# LED-plus35-SHIM.net
KiCad netlist of a schematic drawn in EAGLE
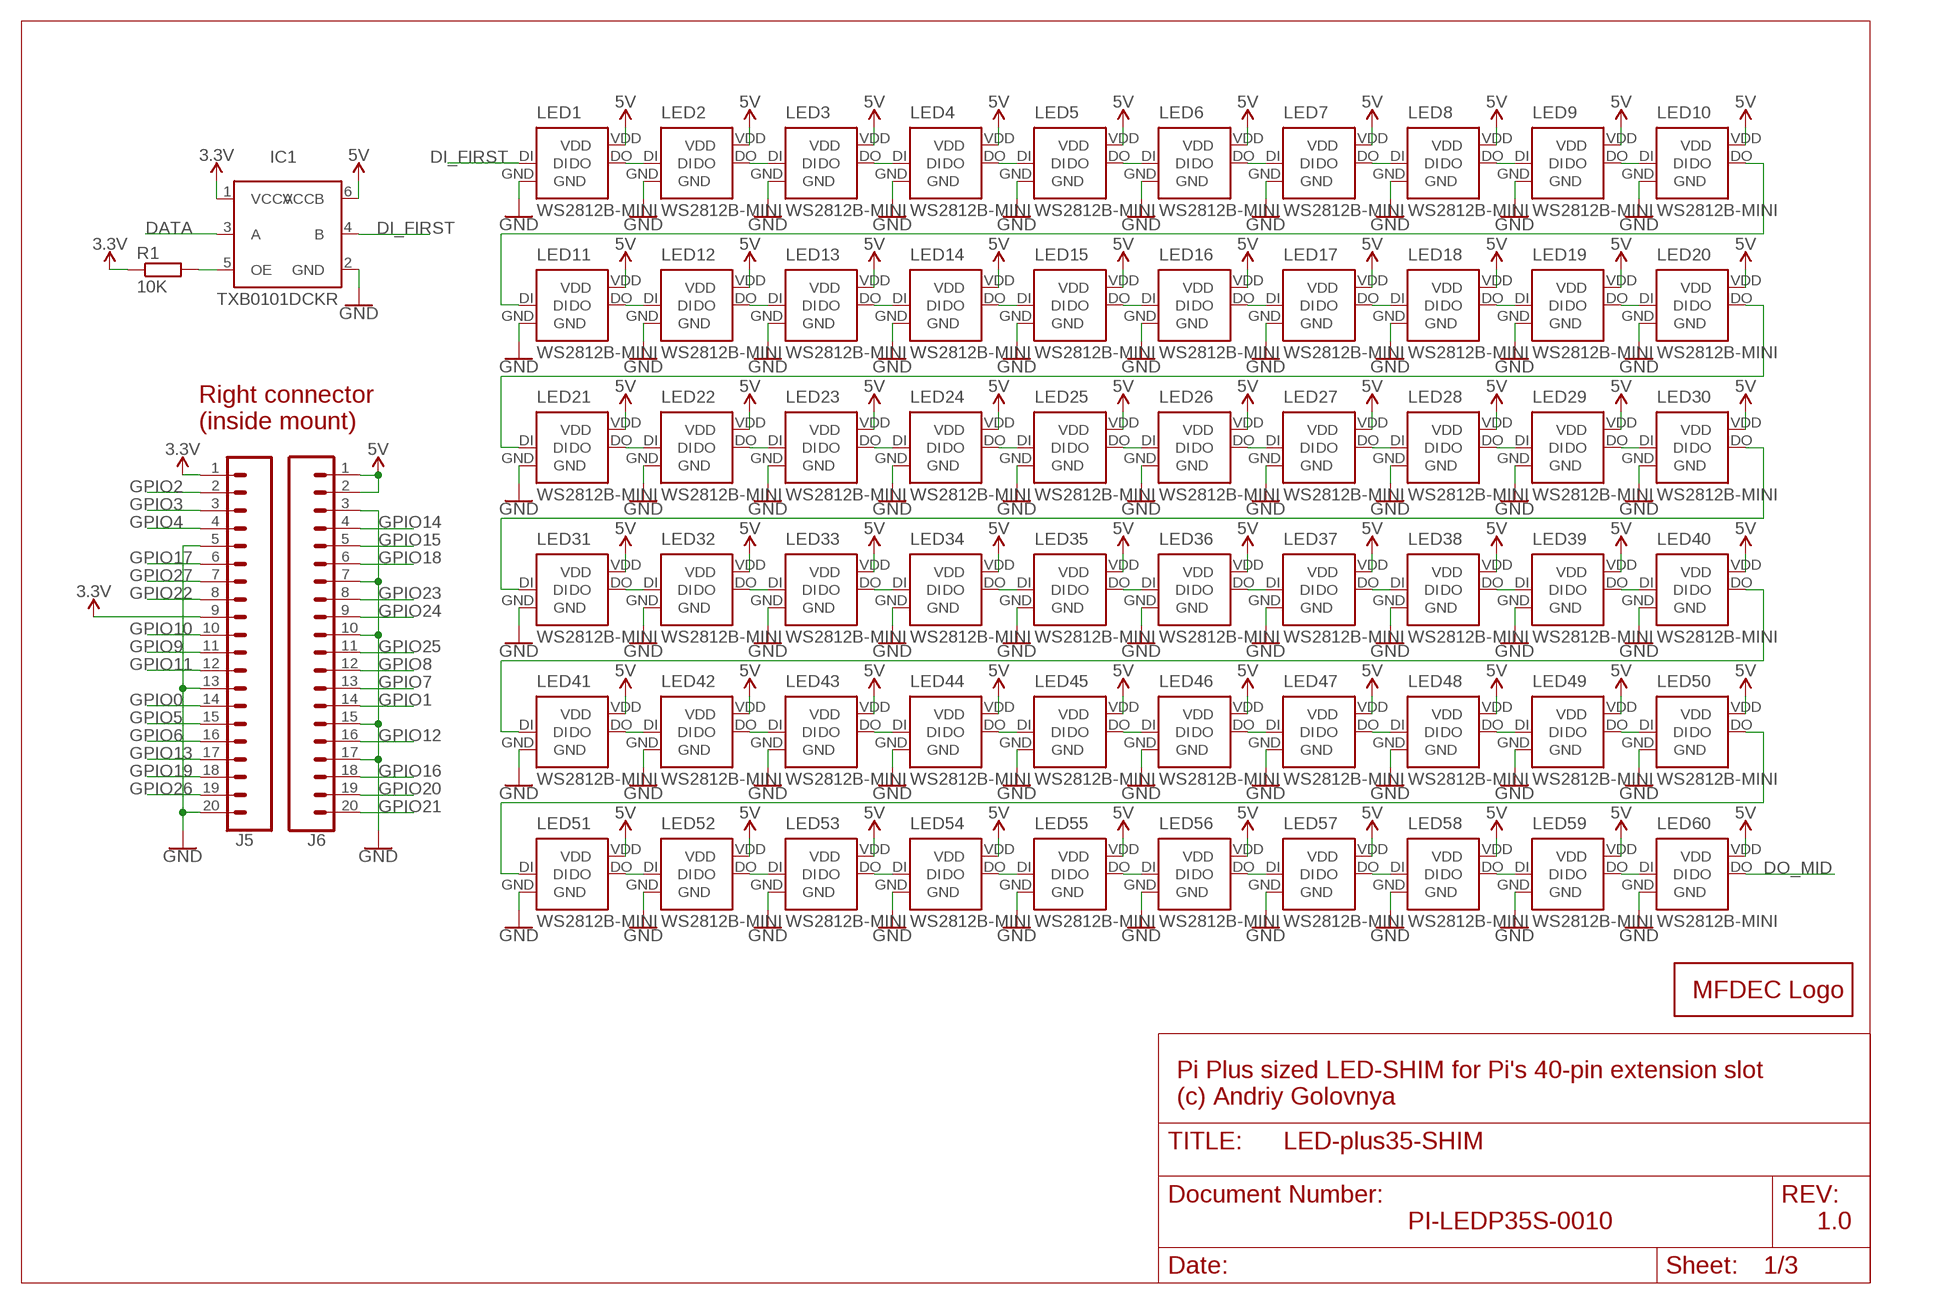
[diagram p0: schematic, sheet 1]
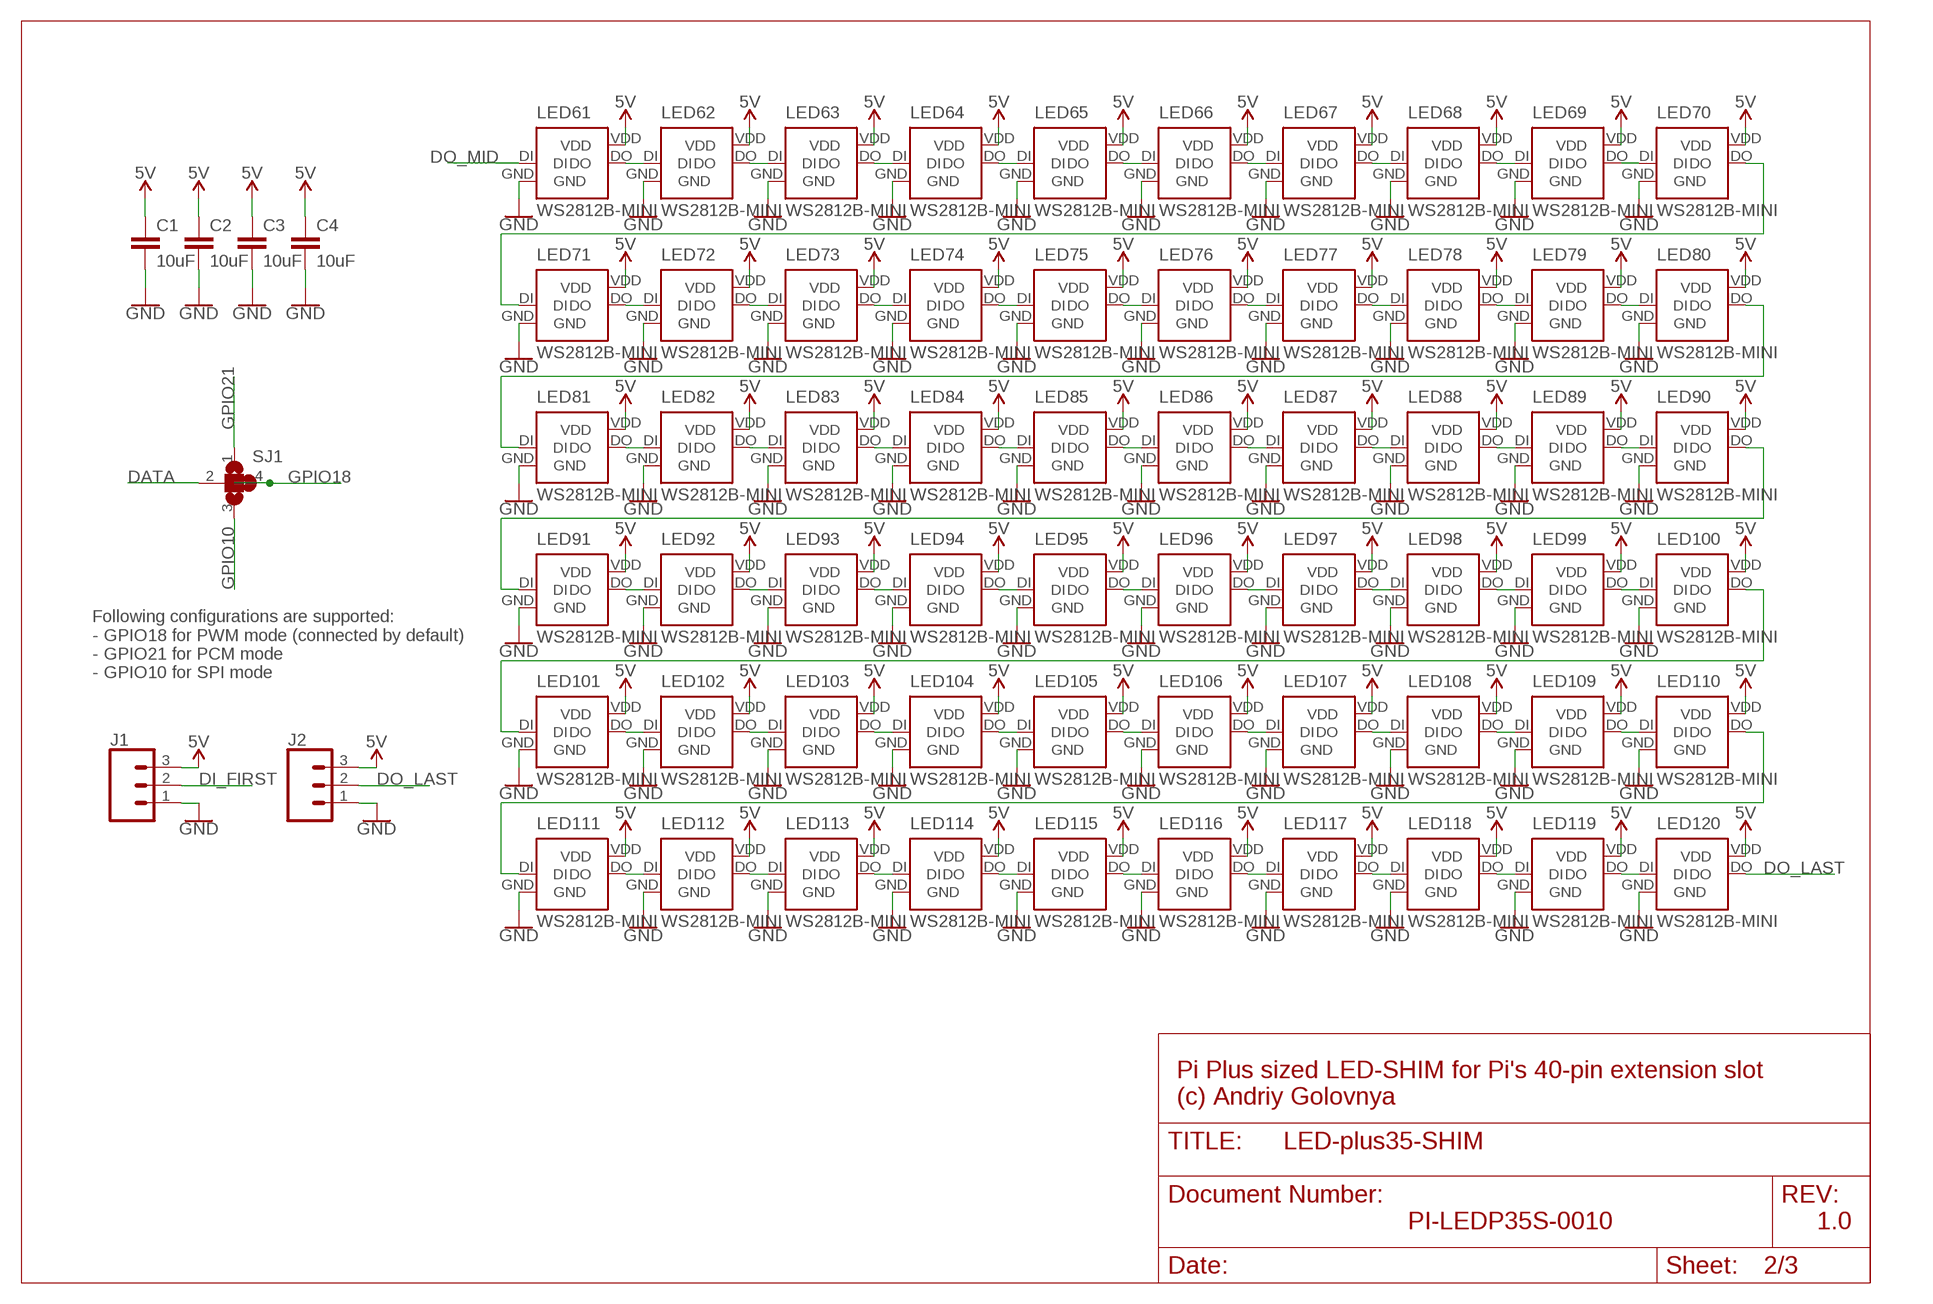
[diagram p1: schematic, sheet 2]
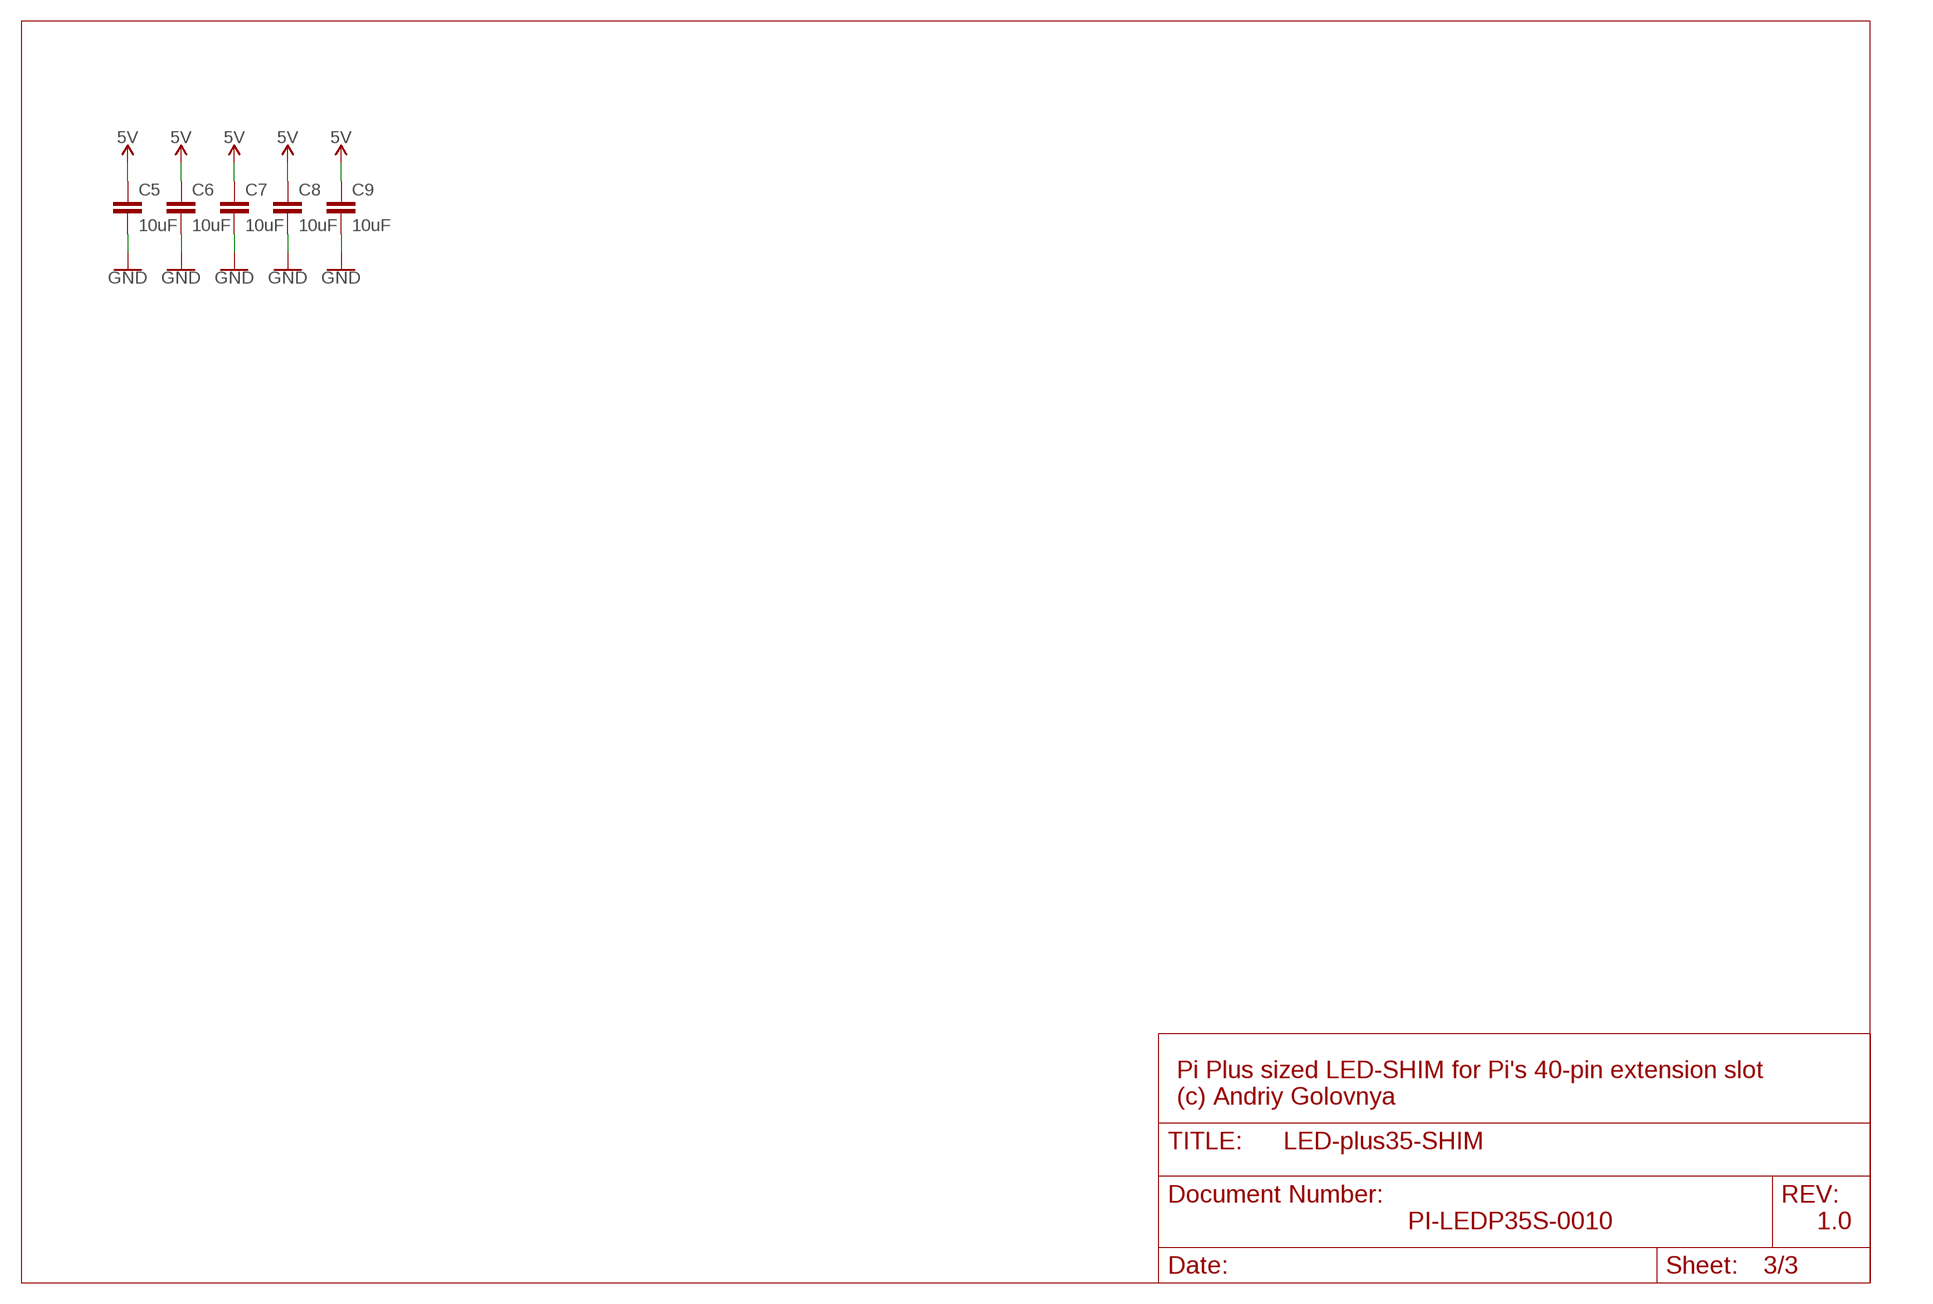
[diagram p2: schematic, sheet 3]

(export (version "E")
  (design (tool "Eeschema 10.0.6"))
  (components
    (comp (ref "C5")
      (value "10uF")
      (footprint "eagle-import:C0805")
      (libsource (lib "eagle-import") (part "C-EUC0805"))
    )
    (comp (ref "C6")
      (value "10uF")
      (footprint "eagle-import:C0805")
      (libsource (lib "eagle-import") (part "C-EUC0805"))
    )
    (comp (ref "C7")
      (value "10uF")
      (footprint "eagle-import:C0805")
      (libsource (lib "eagle-import") (part "C-EUC0805"))
    )
    (comp (ref "C8")
      (value "10uF")
      (footprint "eagle-import:C0805")
      (libsource (lib "eagle-import") (part "C-EUC0805"))
    )
    (comp (ref "C9")
      (value "10uF")
      (footprint "eagle-import:C0805")
      (libsource (lib "eagle-import") (part "C-EUC0805"))
    )
    (comp (ref "IC1")
      (value "TXB0101DCKR")
      (footprint "eagle-import:SOT65P210X110-6N")
      (libsource (lib "eagle-import") (part "TXB0101DCKR"))
    )
    (comp (ref "J5")
      (value "CONN_20LOCK")
      (footprint "eagle-import:1X20_LOCK")
      (libsource (lib "eagle-import") (part "CONN_20LOCK"))
    )
    (comp (ref "J6")
      (value "CONN_20LOCK")
      (footprint "eagle-import:1X20_LOCK")
      (libsource (lib "eagle-import") (part "CONN_20LOCK"))
    )
    (comp (ref "LED1")
      (value "WS2812B-MINI")
      (footprint "eagle-import:WS2812X-MINI")
      (libsource (lib "eagle-import") (part "WS2812B-MINI"))
    )
    (comp (ref "LED2")
      (value "WS2812B-MINI")
      (footprint "eagle-import:WS2812X-MINI")
      (libsource (lib "eagle-import") (part "WS2812B-MINI"))
    )
    (comp (ref "LED3")
      (value "WS2812B-MINI")
      (footprint "eagle-import:WS2812X-MINI")
      (libsource (lib "eagle-import") (part "WS2812B-MINI"))
    )
    (comp (ref "LED4")
      (value "WS2812B-MINI")
      (footprint "eagle-import:WS2812X-MINI")
      (libsource (lib "eagle-import") (part "WS2812B-MINI"))
    )
    (comp (ref "LED5")
      (value "WS2812B-MINI")
      (footprint "eagle-import:WS2812X-MINI")
      (libsource (lib "eagle-import") (part "WS2812B-MINI"))
    )
    (comp (ref "LED6")
      (value "WS2812B-MINI")
      (footprint "eagle-import:WS2812X-MINI")
      (libsource (lib "eagle-import") (part "WS2812B-MINI"))
    )
    (comp (ref "LED7")
      (value "WS2812B-MINI")
      (footprint "eagle-import:WS2812X-MINI")
      (libsource (lib "eagle-import") (part "WS2812B-MINI"))
    )
    (comp (ref "LED8")
      (value "WS2812B-MINI")
      (footprint "eagle-import:WS2812X-MINI")
      (libsource (lib "eagle-import") (part "WS2812B-MINI"))
    )
    (comp (ref "LED9")
      (value "WS2812B-MINI")
      (footprint "eagle-import:WS2812X-MINI")
      (libsource (lib "eagle-import") (part "WS2812B-MINI"))
    )
    (comp (ref "LED10")
      (value "WS2812B-MINI")
      (footprint "eagle-import:WS2812X-MINI")
      (libsource (lib "eagle-import") (part "WS2812B-MINI"))
    )
    (comp (ref "LED11")
      (value "WS2812B-MINI")
      (footprint "eagle-import:WS2812X-MINI")
      (libsource (lib "eagle-import") (part "WS2812B-MINI"))
    )
    (comp (ref "LED12")
      (value "WS2812B-MINI")
      (footprint "eagle-import:WS2812X-MINI")
      (libsource (lib "eagle-import") (part "WS2812B-MINI"))
    )
    (comp (ref "LED13")
      (value "WS2812B-MINI")
      (footprint "eagle-import:WS2812X-MINI")
      (libsource (lib "eagle-import") (part "WS2812B-MINI"))
    )
    (comp (ref "LED14")
      (value "WS2812B-MINI")
      (footprint "eagle-import:WS2812X-MINI")
      (libsource (lib "eagle-import") (part "WS2812B-MINI"))
    )
    (comp (ref "LED15")
      (value "WS2812B-MINI")
      (footprint "eagle-import:WS2812X-MINI")
      (libsource (lib "eagle-import") (part "WS2812B-MINI"))
    )
    (comp (ref "LED16")
      (value "WS2812B-MINI")
      (footprint "eagle-import:WS2812X-MINI")
      (libsource (lib "eagle-import") (part "WS2812B-MINI"))
    )
    (comp (ref "LED17")
      (value "WS2812B-MINI")
      (footprint "eagle-import:WS2812X-MINI")
      (libsource (lib "eagle-import") (part "WS2812B-MINI"))
    )
    (comp (ref "LED18")
      (value "WS2812B-MINI")
      (footprint "eagle-import:WS2812X-MINI")
      (libsource (lib "eagle-import") (part "WS2812B-MINI"))
    )
    (comp (ref "LED19")
      (value "WS2812B-MINI")
      (footprint "eagle-import:WS2812X-MINI")
      (libsource (lib "eagle-import") (part "WS2812B-MINI"))
    )
    (comp (ref "LED20")
      (value "WS2812B-MINI")
      (footprint "eagle-import:WS2812X-MINI")
      (libsource (lib "eagle-import") (part "WS2812B-MINI"))
    )
    (comp (ref "LED21")
      (value "WS2812B-MINI")
      (footprint "eagle-import:WS2812X-MINI")
      (libsource (lib "eagle-import") (part "WS2812B-MINI"))
    )
    (comp (ref "LED22")
      (value "WS2812B-MINI")
      (footprint "eagle-import:WS2812X-MINI")
      (libsource (lib "eagle-import") (part "WS2812B-MINI"))
    )
    (comp (ref "LED23")
      (value "WS2812B-MINI")
      (footprint "eagle-import:WS2812X-MINI")
      (libsource (lib "eagle-import") (part "WS2812B-MINI"))
    )
    (comp (ref "LED24")
      (value "WS2812B-MINI")
      (footprint "eagle-import:WS2812X-MINI")
      (libsource (lib "eagle-import") (part "WS2812B-MINI"))
    )
    (comp (ref "LED25")
      (value "WS2812B-MINI")
      (footprint "eagle-import:WS2812X-MINI")
      (libsource (lib "eagle-import") (part "WS2812B-MINI"))
    )
    (comp (ref "LED26")
      (value "WS2812B-MINI")
      (footprint "eagle-import:WS2812X-MINI")
      (libsource (lib "eagle-import") (part "WS2812B-MINI"))
    )
    (comp (ref "LED27")
      (value "WS2812B-MINI")
      (footprint "eagle-import:WS2812X-MINI")
      (libsource (lib "eagle-import") (part "WS2812B-MINI"))
    )
    (comp (ref "LED28")
      (value "WS2812B-MINI")
      (footprint "eagle-import:WS2812X-MINI")
      (libsource (lib "eagle-import") (part "WS2812B-MINI"))
    )
    (comp (ref "LED29")
      (value "WS2812B-MINI")
      (footprint "eagle-import:WS2812X-MINI")
      (libsource (lib "eagle-import") (part "WS2812B-MINI"))
    )
    (comp (ref "LED30")
      (value "WS2812B-MINI")
      (footprint "eagle-import:WS2812X-MINI")
      (libsource (lib "eagle-import") (part "WS2812B-MINI"))
    )
    (comp (ref "LED31")
      (value "WS2812B-MINI")
      (footprint "eagle-import:WS2812X-MINI")
      (libsource (lib "eagle-import") (part "WS2812B-MINI"))
    )
    (comp (ref "LED32")
      (value "WS2812B-MINI")
      (footprint "eagle-import:WS2812X-MINI")
      (libsource (lib "eagle-import") (part "WS2812B-MINI"))
    )
    (comp (ref "LED33")
      (value "WS2812B-MINI")
      (footprint "eagle-import:WS2812X-MINI")
      (libsource (lib "eagle-import") (part "WS2812B-MINI"))
    )
    (comp (ref "LED34")
      (value "WS2812B-MINI")
      (footprint "eagle-import:WS2812X-MINI")
      (libsource (lib "eagle-import") (part "WS2812B-MINI"))
    )
    (comp (ref "LED35")
      (value "WS2812B-MINI")
      (footprint "eagle-import:WS2812X-MINI")
      (libsource (lib "eagle-import") (part "WS2812B-MINI"))
    )
    (comp (ref "LED36")
      (value "WS2812B-MINI")
      (footprint "eagle-import:WS2812X-MINI")
      (libsource (lib "eagle-import") (part "WS2812B-MINI"))
    )
    (comp (ref "LED37")
      (value "WS2812B-MINI")
      (footprint "eagle-import:WS2812X-MINI")
      (libsource (lib "eagle-import") (part "WS2812B-MINI"))
    )
    (comp (ref "LED38")
      (value "WS2812B-MINI")
      (footprint "eagle-import:WS2812X-MINI")
      (libsource (lib "eagle-import") (part "WS2812B-MINI"))
    )
    (comp (ref "LED39")
      (value "WS2812B-MINI")
      (footprint "eagle-import:WS2812X-MINI")
      (libsource (lib "eagle-import") (part "WS2812B-MINI"))
    )
    (comp (ref "LED40")
      (value "WS2812B-MINI")
      (footprint "eagle-import:WS2812X-MINI")
      (libsource (lib "eagle-import") (part "WS2812B-MINI"))
    )
    (comp (ref "LED41")
      (value "WS2812B-MINI")
      (footprint "eagle-import:WS2812X-MINI")
      (libsource (lib "eagle-import") (part "WS2812B-MINI"))
    )
    (comp (ref "LED42")
      (value "WS2812B-MINI")
      (footprint "eagle-import:WS2812X-MINI")
      (libsource (lib "eagle-import") (part "WS2812B-MINI"))
    )
    (comp (ref "LED43")
      (value "WS2812B-MINI")
      (footprint "eagle-import:WS2812X-MINI")
      (libsource (lib "eagle-import") (part "WS2812B-MINI"))
    )
    (comp (ref "LED44")
      (value "WS2812B-MINI")
      (footprint "eagle-import:WS2812X-MINI")
      (libsource (lib "eagle-import") (part "WS2812B-MINI"))
    )
    (comp (ref "LED45")
      (value "WS2812B-MINI")
      (footprint "eagle-import:WS2812X-MINI")
      (libsource (lib "eagle-import") (part "WS2812B-MINI"))
    )
    (comp (ref "LED46")
      (value "WS2812B-MINI")
      (footprint "eagle-import:WS2812X-MINI")
      (libsource (lib "eagle-import") (part "WS2812B-MINI"))
    )
    (comp (ref "LED47")
      (value "WS2812B-MINI")
      (footprint "eagle-import:WS2812X-MINI")
      (libsource (lib "eagle-import") (part "WS2812B-MINI"))
    )
    (comp (ref "LED48")
      (value "WS2812B-MINI")
      (footprint "eagle-import:WS2812X-MINI")
      (libsource (lib "eagle-import") (part "WS2812B-MINI"))
    )
    (comp (ref "LED49")
      (value "WS2812B-MINI")
      (footprint "eagle-import:WS2812X-MINI")
      (libsource (lib "eagle-import") (part "WS2812B-MINI"))
    )
    (comp (ref "LED50")
      (value "WS2812B-MINI")
      (footprint "eagle-import:WS2812X-MINI")
      (libsource (lib "eagle-import") (part "WS2812B-MINI"))
    )
    (comp (ref "LED51")
      (value "WS2812B-MINI")
      (footprint "eagle-import:WS2812X-MINI")
      (libsource (lib "eagle-import") (part "WS2812B-MINI"))
    )
    (comp (ref "LED52")
      (value "WS2812B-MINI")
      (footprint "eagle-import:WS2812X-MINI")
      (libsource (lib "eagle-import") (part "WS2812B-MINI"))
    )
    (comp (ref "LED53")
      (value "WS2812B-MINI")
      (footprint "eagle-import:WS2812X-MINI")
      (libsource (lib "eagle-import") (part "WS2812B-MINI"))
    )
    (comp (ref "LED54")
      (value "WS2812B-MINI")
      (footprint "eagle-import:WS2812X-MINI")
      (libsource (lib "eagle-import") (part "WS2812B-MINI"))
    )
    (comp (ref "LED55")
      (value "WS2812B-MINI")
      (footprint "eagle-import:WS2812X-MINI")
      (libsource (lib "eagle-import") (part "WS2812B-MINI"))
    )
    (comp (ref "LED56")
      (value "WS2812B-MINI")
      (footprint "eagle-import:WS2812X-MINI")
      (libsource (lib "eagle-import") (part "WS2812B-MINI"))
    )
    (comp (ref "LED57")
      (value "WS2812B-MINI")
      (footprint "eagle-import:WS2812X-MINI")
      (libsource (lib "eagle-import") (part "WS2812B-MINI"))
    )
    (comp (ref "LED58")
      (value "WS2812B-MINI")
      (footprint "eagle-import:WS2812X-MINI")
      (libsource (lib "eagle-import") (part "WS2812B-MINI"))
    )
    (comp (ref "LED59")
      (value "WS2812B-MINI")
      (footprint "eagle-import:WS2812X-MINI")
      (libsource (lib "eagle-import") (part "WS2812B-MINI"))
    )
    (comp (ref "LED60")
      (value "WS2812B-MINI")
      (footprint "eagle-import:WS2812X-MINI")
      (libsource (lib "eagle-import") (part "WS2812B-MINI"))
    )
    (comp (ref "LOGO1")
      (value "MFDECLOGO_L_40MM")
      (footprint "eagle-import:MFDEC_L_40MM")
      (libsource (lib "eagle-import") (part "MFDECLOGO_L_40MM"))
    )
    (comp (ref "R1")
      (value "10K")
      (footprint "eagle-import:R0402")
      (libsource (lib "eagle-import") (part "R-EU_R0402"))
    )
    (comp (ref "C1")
      (value "10uF")
      (footprint "eagle-import:C0805")
      (libsource (lib "eagle-import") (part "C-EUC0805"))
    )
    (comp (ref "C2")
      (value "10uF")
      (footprint "eagle-import:C0805")
      (libsource (lib "eagle-import") (part "C-EUC0805"))
    )
    (comp (ref "C3")
      (value "10uF")
      (footprint "eagle-import:C0805")
      (libsource (lib "eagle-import") (part "C-EUC0805"))
    )
    (comp (ref "C4")
      (value "10uF")
      (footprint "eagle-import:C0805")
      (libsource (lib "eagle-import") (part "C-EUC0805"))
    )
    (comp (ref "J1")
      (value "CONN_03")
      (footprint "eagle-import:1X03")
      (libsource (lib "eagle-import") (part "CONN_03"))
    )
    (comp (ref "J2")
      (value "CONN_03")
      (footprint "eagle-import:1X03")
      (libsource (lib "eagle-import") (part "CONN_03"))
    )
    (comp (ref "LED61")
      (value "WS2812B-MINI")
      (footprint "eagle-import:WS2812X-MINI")
      (libsource (lib "eagle-import") (part "WS2812B-MINI"))
    )
    (comp (ref "LED62")
      (value "WS2812B-MINI")
      (footprint "eagle-import:WS2812X-MINI")
      (libsource (lib "eagle-import") (part "WS2812B-MINI"))
    )
    (comp (ref "LED63")
      (value "WS2812B-MINI")
      (footprint "eagle-import:WS2812X-MINI")
      (libsource (lib "eagle-import") (part "WS2812B-MINI"))
    )
    (comp (ref "LED64")
      (value "WS2812B-MINI")
      (footprint "eagle-import:WS2812X-MINI")
      (libsource (lib "eagle-import") (part "WS2812B-MINI"))
    )
    (comp (ref "LED65")
      (value "WS2812B-MINI")
      (footprint "eagle-import:WS2812X-MINI")
      (libsource (lib "eagle-import") (part "WS2812B-MINI"))
    )
    (comp (ref "LED66")
      (value "WS2812B-MINI")
      (footprint "eagle-import:WS2812X-MINI")
      (libsource (lib "eagle-import") (part "WS2812B-MINI"))
    )
    (comp (ref "LED67")
      (value "WS2812B-MINI")
      (footprint "eagle-import:WS2812X-MINI")
      (libsource (lib "eagle-import") (part "WS2812B-MINI"))
    )
    (comp (ref "LED68")
      (value "WS2812B-MINI")
      (footprint "eagle-import:WS2812X-MINI")
      (libsource (lib "eagle-import") (part "WS2812B-MINI"))
    )
    (comp (ref "LED69")
      (value "WS2812B-MINI")
      (footprint "eagle-import:WS2812X-MINI")
      (libsource (lib "eagle-import") (part "WS2812B-MINI"))
    )
    (comp (ref "LED70")
      (value "WS2812B-MINI")
      (footprint "eagle-import:WS2812X-MINI")
      (libsource (lib "eagle-import") (part "WS2812B-MINI"))
    )
    (comp (ref "LED71")
      (value "WS2812B-MINI")
      (footprint "eagle-import:WS2812X-MINI")
      (libsource (lib "eagle-import") (part "WS2812B-MINI"))
    )
    (comp (ref "LED72")
      (value "WS2812B-MINI")
      (footprint "eagle-import:WS2812X-MINI")
      (libsource (lib "eagle-import") (part "WS2812B-MINI"))
    )
    (comp (ref "LED73")
      (value "WS2812B-MINI")
      (footprint "eagle-import:WS2812X-MINI")
      (libsource (lib "eagle-import") (part "WS2812B-MINI"))
    )
    (comp (ref "LED74")
      (value "WS2812B-MINI")
      (footprint "eagle-import:WS2812X-MINI")
      (libsource (lib "eagle-import") (part "WS2812B-MINI"))
    )
    (comp (ref "LED75")
      (value "WS2812B-MINI")
      (footprint "eagle-import:WS2812X-MINI")
      (libsource (lib "eagle-import") (part "WS2812B-MINI"))
    )
    (comp (ref "LED76")
      (value "WS2812B-MINI")
      (footprint "eagle-import:WS2812X-MINI")
      (libsource (lib "eagle-import") (part "WS2812B-MINI"))
    )
    (comp (ref "LED77")
      (value "WS2812B-MINI")
      (footprint "eagle-import:WS2812X-MINI")
      (libsource (lib "eagle-import") (part "WS2812B-MINI"))
    )
    (comp (ref "LED78")
      (value "WS2812B-MINI")
      (footprint "eagle-import:WS2812X-MINI")
      (libsource (lib "eagle-import") (part "WS2812B-MINI"))
    )
    (comp (ref "LED79")
      (value "WS2812B-MINI")
      (footprint "eagle-import:WS2812X-MINI")
      (libsource (lib "eagle-import") (part "WS2812B-MINI"))
    )
    (comp (ref "LED80")
      (value "WS2812B-MINI")
      (footprint "eagle-import:WS2812X-MINI")
      (libsource (lib "eagle-import") (part "WS2812B-MINI"))
    )
    (comp (ref "LED81")
      (value "WS2812B-MINI")
      (footprint "eagle-import:WS2812X-MINI")
      (libsource (lib "eagle-import") (part "WS2812B-MINI"))
    )
    (comp (ref "LED82")
      (value "WS2812B-MINI")
      (footprint "eagle-import:WS2812X-MINI")
      (libsource (lib "eagle-import") (part "WS2812B-MINI"))
    )
    (comp (ref "LED83")
      (value "WS2812B-MINI")
      (footprint "eagle-import:WS2812X-MINI")
      (libsource (lib "eagle-import") (part "WS2812B-MINI"))
    )
    (comp (ref "LED84")
      (value "WS2812B-MINI")
      (footprint "eagle-import:WS2812X-MINI")
      (libsource (lib "eagle-import") (part "WS2812B-MINI"))
    )
    (comp (ref "LED85")
      (value "WS2812B-MINI")
      (footprint "eagle-import:WS2812X-MINI")
      (libsource (lib "eagle-import") (part "WS2812B-MINI"))
    )
    (comp (ref "LED86")
      (value "WS2812B-MINI")
      (footprint "eagle-import:WS2812X-MINI")
      (libsource (lib "eagle-import") (part "WS2812B-MINI"))
    )
    (comp (ref "LED87")
      (value "WS2812B-MINI")
      (footprint "eagle-import:WS2812X-MINI")
      (libsource (lib "eagle-import") (part "WS2812B-MINI"))
    )
    (comp (ref "LED88")
      (value "WS2812B-MINI")
      (footprint "eagle-import:WS2812X-MINI")
      (libsource (lib "eagle-import") (part "WS2812B-MINI"))
    )
    (comp (ref "LED89")
      (value "WS2812B-MINI")
      (footprint "eagle-import:WS2812X-MINI")
      (libsource (lib "eagle-import") (part "WS2812B-MINI"))
    )
    (comp (ref "LED90")
      (value "WS2812B-MINI")
      (footprint "eagle-import:WS2812X-MINI")
      (libsource (lib "eagle-import") (part "WS2812B-MINI"))
    )
    (comp (ref "LED91")
      (value "WS2812B-MINI")
      (footprint "eagle-import:WS2812X-MINI")
      (libsource (lib "eagle-import") (part "WS2812B-MINI"))
    )
    (comp (ref "LED92")
      (value "WS2812B-MINI")
      (footprint "eagle-import:WS2812X-MINI")
      (libsource (lib "eagle-import") (part "WS2812B-MINI"))
    )
    (comp (ref "LED93")
      (value "WS2812B-MINI")
      (footprint "eagle-import:WS2812X-MINI")
      (libsource (lib "eagle-import") (part "WS2812B-MINI"))
    )
    (comp (ref "LED94")
      (value "WS2812B-MINI")
      (footprint "eagle-import:WS2812X-MINI")
      (libsource (lib "eagle-import") (part "WS2812B-MINI"))
    )
    (comp (ref "LED95")
      (value "WS2812B-MINI")
      (footprint "eagle-import:WS2812X-MINI")
      (libsource (lib "eagle-import") (part "WS2812B-MINI"))
    )
    (comp (ref "LED96")
      (value "WS2812B-MINI")
      (footprint "eagle-import:WS2812X-MINI")
      (libsource (lib "eagle-import") (part "WS2812B-MINI"))
    )
    (comp (ref "LED97")
      (value "WS2812B-MINI")
      (footprint "eagle-import:WS2812X-MINI")
      (libsource (lib "eagle-import") (part "WS2812B-MINI"))
    )
    (comp (ref "LED98")
      (value "WS2812B-MINI")
      (footprint "eagle-import:WS2812X-MINI")
      (libsource (lib "eagle-import") (part "WS2812B-MINI"))
    )
    (comp (ref "LED99")
      (value "WS2812B-MINI")
      (footprint "eagle-import:WS2812X-MINI")
      (libsource (lib "eagle-import") (part "WS2812B-MINI"))
    )
    (comp (ref "LED100")
      (value "WS2812B-MINI")
      (footprint "eagle-import:WS2812X-MINI")
      (libsource (lib "eagle-import") (part "WS2812B-MINI"))
    )
    (comp (ref "LED101")
      (value "WS2812B-MINI")
      (footprint "eagle-import:WS2812X-MINI")
      (libsource (lib "eagle-import") (part "WS2812B-MINI"))
    )
    (comp (ref "LED102")
      (value "WS2812B-MINI")
      (footprint "eagle-import:WS2812X-MINI")
      (libsource (lib "eagle-import") (part "WS2812B-MINI"))
    )
    (comp (ref "LED103")
      (value "WS2812B-MINI")
      (footprint "eagle-import:WS2812X-MINI")
      (libsource (lib "eagle-import") (part "WS2812B-MINI"))
    )
    (comp (ref "LED104")
      (value "WS2812B-MINI")
      (footprint "eagle-import:WS2812X-MINI")
      (libsource (lib "eagle-import") (part "WS2812B-MINI"))
    )
    (comp (ref "LED105")
      (value "WS2812B-MINI")
      (footprint "eagle-import:WS2812X-MINI")
      (libsource (lib "eagle-import") (part "WS2812B-MINI"))
    )
    (comp (ref "LED106")
      (value "WS2812B-MINI")
      (footprint "eagle-import:WS2812X-MINI")
      (libsource (lib "eagle-import") (part "WS2812B-MINI"))
    )
    (comp (ref "LED107")
      (value "WS2812B-MINI")
      (footprint "eagle-import:WS2812X-MINI")
      (libsource (lib "eagle-import") (part "WS2812B-MINI"))
    )
    (comp (ref "LED108")
      (value "WS2812B-MINI")
      (footprint "eagle-import:WS2812X-MINI")
      (libsource (lib "eagle-import") (part "WS2812B-MINI"))
    )
    (comp (ref "LED109")
      (value "WS2812B-MINI")
      (footprint "eagle-import:WS2812X-MINI")
      (libsource (lib "eagle-import") (part "WS2812B-MINI"))
    )
    (comp (ref "LED110")
      (value "WS2812B-MINI")
      (footprint "eagle-import:WS2812X-MINI")
      (libsource (lib "eagle-import") (part "WS2812B-MINI"))
    )
    (comp (ref "LED111")
      (value "WS2812B-MINI")
      (footprint "eagle-import:WS2812X-MINI")
      (libsource (lib "eagle-import") (part "WS2812B-MINI"))
    )
    (comp (ref "LED112")
      (value "WS2812B-MINI")
      (footprint "eagle-import:WS2812X-MINI")
      (libsource (lib "eagle-import") (part "WS2812B-MINI"))
    )
    (comp (ref "LED113")
      (value "WS2812B-MINI")
      (footprint "eagle-import:WS2812X-MINI")
      (libsource (lib "eagle-import") (part "WS2812B-MINI"))
    )
    (comp (ref "LED114")
      (value "WS2812B-MINI")
      (footprint "eagle-import:WS2812X-MINI")
      (libsource (lib "eagle-import") (part "WS2812B-MINI"))
    )
    (comp (ref "LED115")
      (value "WS2812B-MINI")
      (footprint "eagle-import:WS2812X-MINI")
      (libsource (lib "eagle-import") (part "WS2812B-MINI"))
    )
    (comp (ref "LED116")
      (value "WS2812B-MINI")
      (footprint "eagle-import:WS2812X-MINI")
      (libsource (lib "eagle-import") (part "WS2812B-MINI"))
    )
    (comp (ref "LED117")
      (value "WS2812B-MINI")
      (footprint "eagle-import:WS2812X-MINI")
      (libsource (lib "eagle-import") (part "WS2812B-MINI"))
    )
    (comp (ref "LED118")
      (value "WS2812B-MINI")
      (footprint "eagle-import:WS2812X-MINI")
      (libsource (lib "eagle-import") (part "WS2812B-MINI"))
    )
    (comp (ref "LED119")
      (value "WS2812B-MINI")
      (footprint "eagle-import:WS2812X-MINI")
      (libsource (lib "eagle-import") (part "WS2812B-MINI"))
    )
    (comp (ref "LED120")
      (value "WS2812B-MINI")
      (footprint "eagle-import:WS2812X-MINI")
      (libsource (lib "eagle-import") (part "WS2812B-MINI"))
    )
    (comp (ref "SJ1")
      (value "SJ3")
      (footprint "eagle-import:SJ_3")
      (libsource (lib "eagle-import") (part "SJ3"))
    )
  )
  (nets
    (net (code "1") (name "3.3V") (class "Default")
      (node (ref "IC1") (pin "1") (pinfunction "VCCA_1") (pintype "power_in"))
      (node (ref "J5") (pin "1") (pinfunction "1_1") (pintype "passive"))
      (node (ref "J5") (pin "9") (pinfunction "9_9") (pintype "passive"))
      (node (ref "R1") (pin "1") (pinfunction "1_1") (pintype "passive"))
    )
    (net (code "2") (name "5V") (class "Default")
      (node (ref "C1") (pin "1") (pinfunction "1_1") (pintype "passive"))
      (node (ref "C2") (pin "1") (pinfunction "1_1") (pintype "passive"))
      (node (ref "C3") (pin "1") (pinfunction "1_1") (pintype "passive"))
      (node (ref "C4") (pin "1") (pinfunction "1_1") (pintype "passive"))
      (node (ref "C5") (pin "1") (pinfunction "1_1") (pintype "passive"))
      (node (ref "C6") (pin "1") (pinfunction "1_1") (pintype "passive"))
      (node (ref "C7") (pin "1") (pinfunction "1_1") (pintype "passive"))
      (node (ref "C8") (pin "1") (pinfunction "1_1") (pintype "passive"))
      (node (ref "C9") (pin "1") (pinfunction "1_1") (pintype "passive"))
      (node (ref "IC1") (pin "6") (pinfunction "VCCB_6") (pintype "power_in"))
      (node (ref "J1") (pin "3") (pinfunction "3_3") (pintype "passive"))
      (node (ref "J2") (pin "3") (pinfunction "3_3") (pintype "passive"))
      (node (ref "J6") (pin "1") (pinfunction "1_1") (pintype "passive"))
      (node (ref "J6") (pin "2") (pinfunction "2_2") (pintype "passive"))
      (node (ref "LED1") (pin "VDD") (pinfunction "VDD_VDD") (pintype "power_in"))
      (node (ref "LED10") (pin "VDD") (pinfunction "VDD_VDD") (pintype "power_in"))
      (node (ref "LED100") (pin "VDD") (pinfunction "VDD_VDD") (pintype "power_in"))
      (node (ref "LED101") (pin "VDD") (pinfunction "VDD_VDD") (pintype "power_in"))
      (node (ref "LED102") (pin "VDD") (pinfunction "VDD_VDD") (pintype "power_in"))
      (node (ref "LED103") (pin "VDD") (pinfunction "VDD_VDD") (pintype "power_in"))
      (node (ref "LED104") (pin "VDD") (pinfunction "VDD_VDD") (pintype "power_in"))
      (node (ref "LED105") (pin "VDD") (pinfunction "VDD_VDD") (pintype "power_in"))
      (node (ref "LED106") (pin "VDD") (pinfunction "VDD_VDD") (pintype "power_in"))
      (node (ref "LED107") (pin "VDD") (pinfunction "VDD_VDD") (pintype "power_in"))
      (node (ref "LED108") (pin "VDD") (pinfunction "VDD_VDD") (pintype "power_in"))
      (node (ref "LED109") (pin "VDD") (pinfunction "VDD_VDD") (pintype "power_in"))
      (node (ref "LED11") (pin "VDD") (pinfunction "VDD_VDD") (pintype "power_in"))
      (node (ref "LED110") (pin "VDD") (pinfunction "VDD_VDD") (pintype "power_in"))
      (node (ref "LED111") (pin "VDD") (pinfunction "VDD_VDD") (pintype "power_in"))
      (node (ref "LED112") (pin "VDD") (pinfunction "VDD_VDD") (pintype "power_in"))
      (node (ref "LED113") (pin "VDD") (pinfunction "VDD_VDD") (pintype "power_in"))
      (node (ref "LED114") (pin "VDD") (pinfunction "VDD_VDD") (pintype "power_in"))
      (node (ref "LED115") (pin "VDD") (pinfunction "VDD_VDD") (pintype "power_in"))
      (node (ref "LED116") (pin "VDD") (pinfunction "VDD_VDD") (pintype "power_in"))
      (node (ref "LED117") (pin "VDD") (pinfunction "VDD_VDD") (pintype "power_in"))
      (node (ref "LED118") (pin "VDD") (pinfunction "VDD_VDD") (pintype "power_in"))
      (node (ref "LED119") (pin "VDD") (pinfunction "VDD_VDD") (pintype "power_in"))
      (node (ref "LED12") (pin "VDD") (pinfunction "VDD_VDD") (pintype "power_in"))
      (node (ref "LED120") (pin "VDD") (pinfunction "VDD_VDD") (pintype "power_in"))
      (node (ref "LED13") (pin "VDD") (pinfunction "VDD_VDD") (pintype "power_in"))
      (node (ref "LED14") (pin "VDD") (pinfunction "VDD_VDD") (pintype "power_in"))
      (node (ref "LED15") (pin "VDD") (pinfunction "VDD_VDD") (pintype "power_in"))
      (node (ref "LED16") (pin "VDD") (pinfunction "VDD_VDD") (pintype "power_in"))
      (node (ref "LED17") (pin "VDD") (pinfunction "VDD_VDD") (pintype "power_in"))
      (node (ref "LED18") (pin "VDD") (pinfunction "VDD_VDD") (pintype "power_in"))
      (node (ref "LED19") (pin "VDD") (pinfunction "VDD_VDD") (pintype "power_in"))
      (node (ref "LED2") (pin "VDD") (pinfunction "VDD_VDD") (pintype "power_in"))
      (node (ref "LED20") (pin "VDD") (pinfunction "VDD_VDD") (pintype "power_in"))
      (node (ref "LED21") (pin "VDD") (pinfunction "VDD_VDD") (pintype "power_in"))
      (node (ref "LED22") (pin "VDD") (pinfunction "VDD_VDD") (pintype "power_in"))
      (node (ref "LED23") (pin "VDD") (pinfunction "VDD_VDD") (pintype "power_in"))
      (node (ref "LED24") (pin "VDD") (pinfunction "VDD_VDD") (pintype "power_in"))
      (node (ref "LED25") (pin "VDD") (pinfunction "VDD_VDD") (pintype "power_in"))
      (node (ref "LED26") (pin "VDD") (pinfunction "VDD_VDD") (pintype "power_in"))
      (node (ref "LED27") (pin "VDD") (pinfunction "VDD_VDD") (pintype "power_in"))
      (node (ref "LED28") (pin "VDD") (pinfunction "VDD_VDD") (pintype "power_in"))
      (node (ref "LED29") (pin "VDD") (pinfunction "VDD_VDD") (pintype "power_in"))
      (node (ref "LED3") (pin "VDD") (pinfunction "VDD_VDD") (pintype "power_in"))
      (node (ref "LED30") (pin "VDD") (pinfunction "VDD_VDD") (pintype "power_in"))
      (node (ref "LED31") (pin "VDD") (pinfunction "VDD_VDD") (pintype "power_in"))
      (node (ref "LED32") (pin "VDD") (pinfunction "VDD_VDD") (pintype "power_in"))
      (node (ref "LED33") (pin "VDD") (pinfunction "VDD_VDD") (pintype "power_in"))
      (node (ref "LED34") (pin "VDD") (pinfunction "VDD_VDD") (pintype "power_in"))
      (node (ref "LED35") (pin "VDD") (pinfunction "VDD_VDD") (pintype "power_in"))
      (node (ref "LED36") (pin "VDD") (pinfunction "VDD_VDD") (pintype "power_in"))
      (node (ref "LED37") (pin "VDD") (pinfunction "VDD_VDD") (pintype "power_in"))
      (node (ref "LED38") (pin "VDD") (pinfunction "VDD_VDD") (pintype "power_in"))
      (node (ref "LED39") (pin "VDD") (pinfunction "VDD_VDD") (pintype "power_in"))
      (node (ref "LED4") (pin "VDD") (pinfunction "VDD_VDD") (pintype "power_in"))
      (node (ref "LED40") (pin "VDD") (pinfunction "VDD_VDD") (pintype "power_in"))
      (node (ref "LED41") (pin "VDD") (pinfunction "VDD_VDD") (pintype "power_in"))
      (node (ref "LED42") (pin "VDD") (pinfunction "VDD_VDD") (pintype "power_in"))
      (node (ref "LED43") (pin "VDD") (pinfunction "VDD_VDD") (pintype "power_in"))
      (node (ref "LED44") (pin "VDD") (pinfunction "VDD_VDD") (pintype "power_in"))
      (node (ref "LED45") (pin "VDD") (pinfunction "VDD_VDD") (pintype "power_in"))
      (node (ref "LED46") (pin "VDD") (pinfunction "VDD_VDD") (pintype "power_in"))
      (node (ref "LED47") (pin "VDD") (pinfunction "VDD_VDD") (pintype "power_in"))
      (node (ref "LED48") (pin "VDD") (pinfunction "VDD_VDD") (pintype "power_in"))
      (node (ref "LED49") (pin "VDD") (pinfunction "VDD_VDD") (pintype "power_in"))
      (node (ref "LED5") (pin "VDD") (pinfunction "VDD_VDD") (pintype "power_in"))
      (node (ref "LED50") (pin "VDD") (pinfunction "VDD_VDD") (pintype "power_in"))
      (node (ref "LED51") (pin "VDD") (pinfunction "VDD_VDD") (pintype "power_in"))
      (node (ref "LED52") (pin "VDD") (pinfunction "VDD_VDD") (pintype "power_in"))
      (node (ref "LED53") (pin "VDD") (pinfunction "VDD_VDD") (pintype "power_in"))
      (node (ref "LED54") (pin "VDD") (pinfunction "VDD_VDD") (pintype "power_in"))
      (node (ref "LED55") (pin "VDD") (pinfunction "VDD_VDD") (pintype "power_in"))
      (node (ref "LED56") (pin "VDD") (pinfunction "VDD_VDD") (pintype "power_in"))
      (node (ref "LED57") (pin "VDD") (pinfunction "VDD_VDD") (pintype "power_in"))
      (node (ref "LED58") (pin "VDD") (pinfunction "VDD_VDD") (pintype "power_in"))
      (node (ref "LED59") (pin "VDD") (pinfunction "VDD_VDD") (pintype "power_in"))
      (node (ref "LED6") (pin "VDD") (pinfunction "VDD_VDD") (pintype "power_in"))
      (node (ref "LED60") (pin "VDD") (pinfunction "VDD_VDD") (pintype "power_in"))
      (node (ref "LED61") (pin "VDD") (pinfunction "VDD_VDD") (pintype "power_in"))
      (node (ref "LED62") (pin "VDD") (pinfunction "VDD_VDD") (pintype "power_in"))
      (node (ref "LED63") (pin "VDD") (pinfunction "VDD_VDD") (pintype "power_in"))
      (node (ref "LED64") (pin "VDD") (pinfunction "VDD_VDD") (pintype "power_in"))
      (node (ref "LED65") (pin "VDD") (pinfunction "VDD_VDD") (pintype "power_in"))
      (node (ref "LED66") (pin "VDD") (pinfunction "VDD_VDD") (pintype "power_in"))
      (node (ref "LED67") (pin "VDD") (pinfunction "VDD_VDD") (pintype "power_in"))
      (node (ref "LED68") (pin "VDD") (pinfunction "VDD_VDD") (pintype "power_in"))
      (node (ref "LED69") (pin "VDD") (pinfunction "VDD_VDD") (pintype "power_in"))
      (node (ref "LED7") (pin "VDD") (pinfunction "VDD_VDD") (pintype "power_in"))
      (node (ref "LED70") (pin "VDD") (pinfunction "VDD_VDD") (pintype "power_in"))
      (node (ref "LED71") (pin "VDD") (pinfunction "VDD_VDD") (pintype "power_in"))
      (node (ref "LED72") (pin "VDD") (pinfunction "VDD_VDD") (pintype "power_in"))
      (node (ref "LED73") (pin "VDD") (pinfunction "VDD_VDD") (pintype "power_in"))
      (node (ref "LED74") (pin "VDD") (pinfunction "VDD_VDD") (pintype "power_in"))
      (node (ref "LED75") (pin "VDD") (pinfunction "VDD_VDD") (pintype "power_in"))
      (node (ref "LED76") (pin "VDD") (pinfunction "VDD_VDD") (pintype "power_in"))
      (node (ref "LED77") (pin "VDD") (pinfunction "VDD_VDD") (pintype "power_in"))
      (node (ref "LED78") (pin "VDD") (pinfunction "VDD_VDD") (pintype "power_in"))
      (node (ref "LED79") (pin "VDD") (pinfunction "VDD_VDD") (pintype "power_in"))
      (node (ref "LED8") (pin "VDD") (pinfunction "VDD_VDD") (pintype "power_in"))
      (node (ref "LED80") (pin "VDD") (pinfunction "VDD_VDD") (pintype "power_in"))
      (node (ref "LED81") (pin "VDD") (pinfunction "VDD_VDD") (pintype "power_in"))
      (node (ref "LED82") (pin "VDD") (pinfunction "VDD_VDD") (pintype "power_in"))
      (node (ref "LED83") (pin "VDD") (pinfunction "VDD_VDD") (pintype "power_in"))
      (node (ref "LED84") (pin "VDD") (pinfunction "VDD_VDD") (pintype "power_in"))
      (node (ref "LED85") (pin "VDD") (pinfunction "VDD_VDD") (pintype "power_in"))
      (node (ref "LED86") (pin "VDD") (pinfunction "VDD_VDD") (pintype "power_in"))
      (node (ref "LED87") (pin "VDD") (pinfunction "VDD_VDD") (pintype "power_in"))
      (node (ref "LED88") (pin "VDD") (pinfunction "VDD_VDD") (pintype "power_in"))
      (node (ref "LED89") (pin "VDD") (pinfunction "VDD_VDD") (pintype "power_in"))
      (node (ref "LED9") (pin "VDD") (pinfunction "VDD_VDD") (pintype "power_in"))
      (node (ref "LED90") (pin "VDD") (pinfunction "VDD_VDD") (pintype "power_in"))
      (node (ref "LED91") (pin "VDD") (pinfunction "VDD_VDD") (pintype "power_in"))
      (node (ref "LED92") (pin "VDD") (pinfunction "VDD_VDD") (pintype "power_in"))
      (node (ref "LED93") (pin "VDD") (pinfunction "VDD_VDD") (pintype "power_in"))
      (node (ref "LED94") (pin "VDD") (pinfunction "VDD_VDD") (pintype "power_in"))
      (node (ref "LED95") (pin "VDD") (pinfunction "VDD_VDD") (pintype "power_in"))
      (node (ref "LED96") (pin "VDD") (pinfunction "VDD_VDD") (pintype "power_in"))
      (node (ref "LED97") (pin "VDD") (pinfunction "VDD_VDD") (pintype "power_in"))
      (node (ref "LED98") (pin "VDD") (pinfunction "VDD_VDD") (pintype "power_in"))
      (node (ref "LED99") (pin "VDD") (pinfunction "VDD_VDD") (pintype "power_in"))
    )
    (net (code "3") (name "DATA") (class "Default")
      (node (ref "IC1") (pin "3") (pinfunction "A_3") (pintype "bidirectional"))
      (node (ref "SJ1") (pin "2") (pinfunction "2_2") (pintype "passive"))
    )
    (net (code "4") (name "DI_FIRST") (class "Default")
      (node (ref "IC1") (pin "4") (pinfunction "B_4") (pintype "bidirectional"))
      (node (ref "J1") (pin "2") (pinfunction "2_2") (pintype "passive"))
      (node (ref "LED1") (pin "DI") (pinfunction "DI_DI") (pintype "input"))
    )
    (net (code "5") (name "DO_LAST") (class "Default")
      (node (ref "J2") (pin "2") (pinfunction "2_2") (pintype "passive"))
      (node (ref "LED120") (pin "DO") (pinfunction "DO_DO") (pintype "output"))
    )
    (net (code "6") (name "DO_MID") (class "Default")
      (node (ref "LED60") (pin "DO") (pinfunction "DO_DO") (pintype "output"))
      (node (ref "LED61") (pin "DI") (pinfunction "DI_DI") (pintype "input"))
    )
    (net (code "7") (name "GND") (class "Default")
      (node (ref "C1") (pin "2") (pinfunction "2_2") (pintype "passive"))
      (node (ref "C2") (pin "2") (pinfunction "2_2") (pintype "passive"))
      (node (ref "C3") (pin "2") (pinfunction "2_2") (pintype "passive"))
      (node (ref "C4") (pin "2") (pinfunction "2_2") (pintype "passive"))
      (node (ref "C5") (pin "2") (pinfunction "2_2") (pintype "passive"))
      (node (ref "C6") (pin "2") (pinfunction "2_2") (pintype "passive"))
      (node (ref "C7") (pin "2") (pinfunction "2_2") (pintype "passive"))
      (node (ref "C8") (pin "2") (pinfunction "2_2") (pintype "passive"))
      (node (ref "C9") (pin "2") (pinfunction "2_2") (pintype "passive"))
      (node (ref "IC1") (pin "2") (pinfunction "GND_2") (pintype "power_in"))
      (node (ref "J1") (pin "1") (pinfunction "1_1") (pintype "passive"))
      (node (ref "J2") (pin "1") (pinfunction "1_1") (pintype "passive"))
      (node (ref "J5") (pin "13") (pinfunction "13_13") (pintype "passive"))
      (node (ref "J5") (pin "20") (pinfunction "20_20") (pintype "passive"))
      (node (ref "J5") (pin "5") (pinfunction "5_5") (pintype "passive"))
      (node (ref "J6") (pin "10") (pinfunction "10_10") (pintype "passive"))
      (node (ref "J6") (pin "15") (pinfunction "15_15") (pintype "passive"))
      (node (ref "J6") (pin "17") (pinfunction "17_17") (pintype "passive"))
      (node (ref "J6") (pin "3") (pinfunction "3_3") (pintype "passive"))
      (node (ref "J6") (pin "7") (pinfunction "7_7") (pintype "passive"))
      (node (ref "LED1") (pin "GND") (pinfunction "GND_GND") (pintype "power_in"))
      (node (ref "LED10") (pin "GND") (pinfunction "GND_GND") (pintype "power_in"))
      (node (ref "LED100") (pin "GND") (pinfunction "GND_GND") (pintype "power_in"))
      (node (ref "LED101") (pin "GND") (pinfunction "GND_GND") (pintype "power_in"))
      (node (ref "LED102") (pin "GND") (pinfunction "GND_GND") (pintype "power_in"))
      (node (ref "LED103") (pin "GND") (pinfunction "GND_GND") (pintype "power_in"))
      (node (ref "LED104") (pin "GND") (pinfunction "GND_GND") (pintype "power_in"))
      (node (ref "LED105") (pin "GND") (pinfunction "GND_GND") (pintype "power_in"))
      (node (ref "LED106") (pin "GND") (pinfunction "GND_GND") (pintype "power_in"))
      (node (ref "LED107") (pin "GND") (pinfunction "GND_GND") (pintype "power_in"))
      (node (ref "LED108") (pin "GND") (pinfunction "GND_GND") (pintype "power_in"))
      (node (ref "LED109") (pin "GND") (pinfunction "GND_GND") (pintype "power_in"))
      (node (ref "LED11") (pin "GND") (pinfunction "GND_GND") (pintype "power_in"))
      (node (ref "LED110") (pin "GND") (pinfunction "GND_GND") (pintype "power_in"))
      (node (ref "LED111") (pin "GND") (pinfunction "GND_GND") (pintype "power_in"))
      (node (ref "LED112") (pin "GND") (pinfunction "GND_GND") (pintype "power_in"))
      (node (ref "LED113") (pin "GND") (pinfunction "GND_GND") (pintype "power_in"))
      (node (ref "LED114") (pin "GND") (pinfunction "GND_GND") (pintype "power_in"))
      (node (ref "LED115") (pin "GND") (pinfunction "GND_GND") (pintype "power_in"))
      (node (ref "LED116") (pin "GND") (pinfunction "GND_GND") (pintype "power_in"))
      (node (ref "LED117") (pin "GND") (pinfunction "GND_GND") (pintype "power_in"))
      (node (ref "LED118") (pin "GND") (pinfunction "GND_GND") (pintype "power_in"))
      (node (ref "LED119") (pin "GND") (pinfunction "GND_GND") (pintype "power_in"))
      (node (ref "LED12") (pin "GND") (pinfunction "GND_GND") (pintype "power_in"))
      (node (ref "LED120") (pin "GND") (pinfunction "GND_GND") (pintype "power_in"))
      (node (ref "LED13") (pin "GND") (pinfunction "GND_GND") (pintype "power_in"))
      (node (ref "LED14") (pin "GND") (pinfunction "GND_GND") (pintype "power_in"))
      (node (ref "LED15") (pin "GND") (pinfunction "GND_GND") (pintype "power_in"))
      (node (ref "LED16") (pin "GND") (pinfunction "GND_GND") (pintype "power_in"))
      (node (ref "LED17") (pin "GND") (pinfunction "GND_GND") (pintype "power_in"))
      (node (ref "LED18") (pin "GND") (pinfunction "GND_GND") (pintype "power_in"))
      (node (ref "LED19") (pin "GND") (pinfunction "GND_GND") (pintype "power_in"))
      (node (ref "LED2") (pin "GND") (pinfunction "GND_GND") (pintype "power_in"))
      (node (ref "LED20") (pin "GND") (pinfunction "GND_GND") (pintype "power_in"))
      (node (ref "LED21") (pin "GND") (pinfunction "GND_GND") (pintype "power_in"))
      (node (ref "LED22") (pin "GND") (pinfunction "GND_GND") (pintype "power_in"))
      (node (ref "LED23") (pin "GND") (pinfunction "GND_GND") (pintype "power_in"))
      (node (ref "LED24") (pin "GND") (pinfunction "GND_GND") (pintype "power_in"))
      (node (ref "LED25") (pin "GND") (pinfunction "GND_GND") (pintype "power_in"))
      (node (ref "LED26") (pin "GND") (pinfunction "GND_GND") (pintype "power_in"))
      (node (ref "LED27") (pin "GND") (pinfunction "GND_GND") (pintype "power_in"))
      (node (ref "LED28") (pin "GND") (pinfunction "GND_GND") (pintype "power_in"))
      (node (ref "LED29") (pin "GND") (pinfunction "GND_GND") (pintype "power_in"))
      (node (ref "LED3") (pin "GND") (pinfunction "GND_GND") (pintype "power_in"))
      (node (ref "LED30") (pin "GND") (pinfunction "GND_GND") (pintype "power_in"))
      (node (ref "LED31") (pin "GND") (pinfunction "GND_GND") (pintype "power_in"))
      (node (ref "LED32") (pin "GND") (pinfunction "GND_GND") (pintype "power_in"))
      (node (ref "LED33") (pin "GND") (pinfunction "GND_GND") (pintype "power_in"))
      (node (ref "LED34") (pin "GND") (pinfunction "GND_GND") (pintype "power_in"))
      (node (ref "LED35") (pin "GND") (pinfunction "GND_GND") (pintype "power_in"))
      (node (ref "LED36") (pin "GND") (pinfunction "GND_GND") (pintype "power_in"))
      (node (ref "LED37") (pin "GND") (pinfunction "GND_GND") (pintype "power_in"))
      (node (ref "LED38") (pin "GND") (pinfunction "GND_GND") (pintype "power_in"))
      (node (ref "LED39") (pin "GND") (pinfunction "GND_GND") (pintype "power_in"))
      (node (ref "LED4") (pin "GND") (pinfunction "GND_GND") (pintype "power_in"))
      (node (ref "LED40") (pin "GND") (pinfunction "GND_GND") (pintype "power_in"))
      (node (ref "LED41") (pin "GND") (pinfunction "GND_GND") (pintype "power_in"))
      (node (ref "LED42") (pin "GND") (pinfunction "GND_GND") (pintype "power_in"))
      (node (ref "LED43") (pin "GND") (pinfunction "GND_GND") (pintype "power_in"))
      (node (ref "LED44") (pin "GND") (pinfunction "GND_GND") (pintype "power_in"))
      (node (ref "LED45") (pin "GND") (pinfunction "GND_GND") (pintype "power_in"))
      (node (ref "LED46") (pin "GND") (pinfunction "GND_GND") (pintype "power_in"))
      (node (ref "LED47") (pin "GND") (pinfunction "GND_GND") (pintype "power_in"))
      (node (ref "LED48") (pin "GND") (pinfunction "GND_GND") (pintype "power_in"))
      (node (ref "LED49") (pin "GND") (pinfunction "GND_GND") (pintype "power_in"))
      (node (ref "LED5") (pin "GND") (pinfunction "GND_GND") (pintype "power_in"))
      (node (ref "LED50") (pin "GND") (pinfunction "GND_GND") (pintype "power_in"))
      (node (ref "LED51") (pin "GND") (pinfunction "GND_GND") (pintype "power_in"))
      (node (ref "LED52") (pin "GND") (pinfunction "GND_GND") (pintype "power_in"))
      (node (ref "LED53") (pin "GND") (pinfunction "GND_GND") (pintype "power_in"))
      (node (ref "LED54") (pin "GND") (pinfunction "GND_GND") (pintype "power_in"))
      (node (ref "LED55") (pin "GND") (pinfunction "GND_GND") (pintype "power_in"))
      (node (ref "LED56") (pin "GND") (pinfunction "GND_GND") (pintype "power_in"))
      (node (ref "LED57") (pin "GND") (pinfunction "GND_GND") (pintype "power_in"))
      (node (ref "LED58") (pin "GND") (pinfunction "GND_GND") (pintype "power_in"))
      (node (ref "LED59") (pin "GND") (pinfunction "GND_GND") (pintype "power_in"))
      (node (ref "LED6") (pin "GND") (pinfunction "GND_GND") (pintype "power_in"))
      (node (ref "LED60") (pin "GND") (pinfunction "GND_GND") (pintype "power_in"))
      (node (ref "LED61") (pin "GND") (pinfunction "GND_GND") (pintype "power_in"))
      (node (ref "LED62") (pin "GND") (pinfunction "GND_GND") (pintype "power_in"))
      (node (ref "LED63") (pin "GND") (pinfunction "GND_GND") (pintype "power_in"))
      (node (ref "LED64") (pin "GND") (pinfunction "GND_GND") (pintype "power_in"))
      (node (ref "LED65") (pin "GND") (pinfunction "GND_GND") (pintype "power_in"))
      (node (ref "LED66") (pin "GND") (pinfunction "GND_GND") (pintype "power_in"))
      (node (ref "LED67") (pin "GND") (pinfunction "GND_GND") (pintype "power_in"))
      (node (ref "LED68") (pin "GND") (pinfunction "GND_GND") (pintype "power_in"))
      (node (ref "LED69") (pin "GND") (pinfunction "GND_GND") (pintype "power_in"))
      (node (ref "LED7") (pin "GND") (pinfunction "GND_GND") (pintype "power_in"))
      (node (ref "LED70") (pin "GND") (pinfunction "GND_GND") (pintype "power_in"))
      (node (ref "LED71") (pin "GND") (pinfunction "GND_GND") (pintype "power_in"))
      (node (ref "LED72") (pin "GND") (pinfunction "GND_GND") (pintype "power_in"))
      (node (ref "LED73") (pin "GND") (pinfunction "GND_GND") (pintype "power_in"))
      (node (ref "LED74") (pin "GND") (pinfunction "GND_GND") (pintype "power_in"))
      (node (ref "LED75") (pin "GND") (pinfunction "GND_GND") (pintype "power_in"))
      (node (ref "LED76") (pin "GND") (pinfunction "GND_GND") (pintype "power_in"))
      (node (ref "LED77") (pin "GND") (pinfunction "GND_GND") (pintype "power_in"))
      (node (ref "LED78") (pin "GND") (pinfunction "GND_GND") (pintype "power_in"))
      (node (ref "LED79") (pin "GND") (pinfunction "GND_GND") (pintype "power_in"))
      (node (ref "LED8") (pin "GND") (pinfunction "GND_GND") (pintype "power_in"))
      (node (ref "LED80") (pin "GND") (pinfunction "GND_GND") (pintype "power_in"))
      (node (ref "LED81") (pin "GND") (pinfunction "GND_GND") (pintype "power_in"))
      (node (ref "LED82") (pin "GND") (pinfunction "GND_GND") (pintype "power_in"))
      (node (ref "LED83") (pin "GND") (pinfunction "GND_GND") (pintype "power_in"))
      (node (ref "LED84") (pin "GND") (pinfunction "GND_GND") (pintype "power_in"))
      (node (ref "LED85") (pin "GND") (pinfunction "GND_GND") (pintype "power_in"))
      (node (ref "LED86") (pin "GND") (pinfunction "GND_GND") (pintype "power_in"))
      (node (ref "LED87") (pin "GND") (pinfunction "GND_GND") (pintype "power_in"))
      (node (ref "LED88") (pin "GND") (pinfunction "GND_GND") (pintype "power_in"))
      (node (ref "LED89") (pin "GND") (pinfunction "GND_GND") (pintype "power_in"))
      (node (ref "LED9") (pin "GND") (pinfunction "GND_GND") (pintype "power_in"))
      (node (ref "LED90") (pin "GND") (pinfunction "GND_GND") (pintype "power_in"))
      (node (ref "LED91") (pin "GND") (pinfunction "GND_GND") (pintype "power_in"))
      (node (ref "LED92") (pin "GND") (pinfunction "GND_GND") (pintype "power_in"))
      (node (ref "LED93") (pin "GND") (pinfunction "GND_GND") (pintype "power_in"))
      (node (ref "LED94") (pin "GND") (pinfunction "GND_GND") (pintype "power_in"))
      (node (ref "LED95") (pin "GND") (pinfunction "GND_GND") (pintype "power_in"))
      (node (ref "LED96") (pin "GND") (pinfunction "GND_GND") (pintype "power_in"))
      (node (ref "LED97") (pin "GND") (pinfunction "GND_GND") (pintype "power_in"))
      (node (ref "LED98") (pin "GND") (pinfunction "GND_GND") (pintype "power_in"))
      (node (ref "LED99") (pin "GND") (pinfunction "GND_GND") (pintype "power_in"))
    )
    (net (code "8") (name "GPIO0") (class "Default")
      (node (ref "J5") (pin "14") (pinfunction "14_14") (pintype "passive"))
    )
    (net (code "9") (name "GPIO1") (class "Default")
      (node (ref "J6") (pin "14") (pinfunction "14_14") (pintype "passive"))
    )
    (net (code "10") (name "GPIO2") (class "Default")
      (node (ref "J5") (pin "2") (pinfunction "2_2") (pintype "passive"))
    )
    (net (code "11") (name "GPIO3") (class "Default")
      (node (ref "J5") (pin "3") (pinfunction "3_3") (pintype "passive"))
    )
    (net (code "12") (name "GPIO4") (class "Default")
      (node (ref "J5") (pin "4") (pinfunction "4_4") (pintype "passive"))
    )
    (net (code "13") (name "GPIO5") (class "Default")
      (node (ref "J5") (pin "15") (pinfunction "15_15") (pintype "passive"))
    )
    (net (code "14") (name "GPIO6") (class "Default")
      (node (ref "J5") (pin "16") (pinfunction "16_16") (pintype "passive"))
    )
    (net (code "15") (name "GPIO7") (class "Default")
      (node (ref "J6") (pin "13") (pinfunction "13_13") (pintype "passive"))
    )
    (net (code "16") (name "GPIO8") (class "Default")
      (node (ref "J6") (pin "12") (pinfunction "12_12") (pintype "passive"))
    )
    (net (code "17") (name "GPIO9") (class "Default")
      (node (ref "J5") (pin "11") (pinfunction "11_11") (pintype "passive"))
    )
    (net (code "18") (name "GPIO10") (class "Default")
      (node (ref "J5") (pin "10") (pinfunction "10_10") (pintype "passive"))
      (node (ref "SJ1") (pin "3") (pinfunction "3_3") (pintype "passive"))
    )
    (net (code "19") (name "GPIO11") (class "Default")
      (node (ref "J5") (pin "12") (pinfunction "12_12") (pintype "passive"))
    )
    (net (code "20") (name "GPIO12") (class "Default")
      (node (ref "J6") (pin "16") (pinfunction "16_16") (pintype "passive"))
    )
    (net (code "21") (name "GPIO13") (class "Default")
      (node (ref "J5") (pin "17") (pinfunction "17_17") (pintype "passive"))
    )
    (net (code "22") (name "GPIO14") (class "Default")
      (node (ref "J6") (pin "4") (pinfunction "4_4") (pintype "passive"))
    )
    (net (code "23") (name "GPIO15") (class "Default")
      (node (ref "J6") (pin "5") (pinfunction "5_5") (pintype "passive"))
    )
    (net (code "24") (name "GPIO16") (class "Default")
      (node (ref "J6") (pin "18") (pinfunction "18_18") (pintype "passive"))
    )
    (net (code "25") (name "GPIO17") (class "Default")
      (node (ref "J5") (pin "6") (pinfunction "6_6") (pintype "passive"))
    )
    (net (code "26") (name "GPIO18") (class "Default")
      (node (ref "J6") (pin "6") (pinfunction "6_6") (pintype "passive"))
      (node (ref "SJ1") (pin "4") (pinfunction "4_4") (pintype "passive"))
    )
    (net (code "27") (name "GPIO19") (class "Default")
      (node (ref "J5") (pin "18") (pinfunction "18_18") (pintype "passive"))
    )
    (net (code "28") (name "GPIO20") (class "Default")
      (node (ref "J6") (pin "19") (pinfunction "19_19") (pintype "passive"))
    )
    (net (code "29") (name "GPIO21") (class "Default")
      (node (ref "J6") (pin "20") (pinfunction "20_20") (pintype "passive"))
      (node (ref "SJ1") (pin "1") (pinfunction "1_1") (pintype "passive"))
    )
    (net (code "30") (name "GPIO22") (class "Default")
      (node (ref "J5") (pin "8") (pinfunction "8_8") (pintype "passive"))
    )
    (net (code "31") (name "GPIO23") (class "Default")
      (node (ref "J6") (pin "8") (pinfunction "8_8") (pintype "passive"))
    )
    (net (code "32") (name "GPIO24") (class "Default")
      (node (ref "J6") (pin "9") (pinfunction "9_9") (pintype "passive"))
    )
    (net (code "33") (name "GPIO25") (class "Default")
      (node (ref "J6") (pin "11") (pinfunction "11_11") (pintype "passive"))
    )
    (net (code "34") (name "GPIO26") (class "Default")
      (node (ref "J5") (pin "19") (pinfunction "19_19") (pintype "passive"))
    )
    (net (code "35") (name "GPIO27") (class "Default")
      (node (ref "J5") (pin "7") (pinfunction "7_7") (pintype "passive"))
    )
    (net (code "36") (name "Net-(IC1-OE)") (class "Default")
      (node (ref "IC1") (pin "5") (pinfunction "OE_5") (pintype "input"))
      (node (ref "R1") (pin "2") (pinfunction "2_2") (pintype "passive"))
    )
    (net (code "37") (name "Net-(LED1-PadDO)") (class "Default")
      (node (ref "LED1") (pin "DO") (pinfunction "DO_DO") (pintype "output"))
      (node (ref "LED2") (pin "DI") (pinfunction "DI_DI") (pintype "input"))
    )
    (net (code "38") (name "Net-(LED2-PadDO)") (class "Default")
      (node (ref "LED2") (pin "DO") (pinfunction "DO_DO") (pintype "output"))
      (node (ref "LED3") (pin "DI") (pinfunction "DI_DI") (pintype "input"))
    )
    (net (code "39") (name "Net-(LED3-PadDO)") (class "Default")
      (node (ref "LED3") (pin "DO") (pinfunction "DO_DO") (pintype "output"))
      (node (ref "LED4") (pin "DI") (pinfunction "DI_DI") (pintype "input"))
    )
    (net (code "40") (name "Net-(LED4-PadDO)") (class "Default")
      (node (ref "LED4") (pin "DO") (pinfunction "DO_DO") (pintype "output"))
      (node (ref "LED5") (pin "DI") (pinfunction "DI_DI") (pintype "input"))
    )
    (net (code "41") (name "Net-(LED5-PadDO)") (class "Default")
      (node (ref "LED5") (pin "DO") (pinfunction "DO_DO") (pintype "output"))
      (node (ref "LED6") (pin "DI") (pinfunction "DI_DI") (pintype "input"))
    )
    (net (code "42") (name "Net-(LED6-PadDO)") (class "Default")
      (node (ref "LED6") (pin "DO") (pinfunction "DO_DO") (pintype "output"))
      (node (ref "LED7") (pin "DI") (pinfunction "DI_DI") (pintype "input"))
    )
    (net (code "43") (name "Net-(LED7-PadDO)") (class "Default")
      (node (ref "LED7") (pin "DO") (pinfunction "DO_DO") (pintype "output"))
      (node (ref "LED8") (pin "DI") (pinfunction "DI_DI") (pintype "input"))
    )
    (net (code "44") (name "Net-(LED8-PadDO)") (class "Default")
      (node (ref "LED8") (pin "DO") (pinfunction "DO_DO") (pintype "output"))
      (node (ref "LED9") (pin "DI") (pinfunction "DI_DI") (pintype "input"))
    )
    (net (code "45") (name "Net-(LED10-PadDI)") (class "Default")
      (node (ref "LED10") (pin "DI") (pinfunction "DI_DI") (pintype "input"))
      (node (ref "LED9") (pin "DO") (pinfunction "DO_DO") (pintype "output"))
    )
    (net (code "46") (name "Net-(LED10-PadDO)") (class "Default")
      (node (ref "LED10") (pin "DO") (pinfunction "DO_DO") (pintype "output"))
      (node (ref "LED11") (pin "DI") (pinfunction "DI_DI") (pintype "input"))
    )
    (net (code "47") (name "Net-(LED11-PadDO)") (class "Default")
      (node (ref "LED11") (pin "DO") (pinfunction "DO_DO") (pintype "output"))
      (node (ref "LED12") (pin "DI") (pinfunction "DI_DI") (pintype "input"))
    )
    (net (code "48") (name "Net-(LED12-PadDO)") (class "Default")
      (node (ref "LED12") (pin "DO") (pinfunction "DO_DO") (pintype "output"))
      (node (ref "LED13") (pin "DI") (pinfunction "DI_DI") (pintype "input"))
    )
    (net (code "49") (name "Net-(LED13-PadDO)") (class "Default")
      (node (ref "LED13") (pin "DO") (pinfunction "DO_DO") (pintype "output"))
      (node (ref "LED14") (pin "DI") (pinfunction "DI_DI") (pintype "input"))
    )
    (net (code "50") (name "Net-(LED14-PadDO)") (class "Default")
      (node (ref "LED14") (pin "DO") (pinfunction "DO_DO") (pintype "output"))
      (node (ref "LED15") (pin "DI") (pinfunction "DI_DI") (pintype "input"))
    )
    (net (code "51") (name "Net-(LED15-PadDO)") (class "Default")
      (node (ref "LED15") (pin "DO") (pinfunction "DO_DO") (pintype "output"))
      (node (ref "LED16") (pin "DI") (pinfunction "DI_DI") (pintype "input"))
    )
    (net (code "52") (name "Net-(LED16-PadDO)") (class "Default")
      (node (ref "LED16") (pin "DO") (pinfunction "DO_DO") (pintype "output"))
      (node (ref "LED17") (pin "DI") (pinfunction "DI_DI") (pintype "input"))
    )
    (net (code "53") (name "Net-(LED17-PadDO)") (class "Default")
      (node (ref "LED17") (pin "DO") (pinfunction "DO_DO") (pintype "output"))
      (node (ref "LED18") (pin "DI") (pinfunction "DI_DI") (pintype "input"))
    )
    (net (code "54") (name "Net-(LED18-PadDO)") (class "Default")
      (node (ref "LED18") (pin "DO") (pinfunction "DO_DO") (pintype "output"))
      (node (ref "LED19") (pin "DI") (pinfunction "DI_DI") (pintype "input"))
    )
    (net (code "55") (name "Net-(LED19-PadDO)") (class "Default")
      (node (ref "LED19") (pin "DO") (pinfunction "DO_DO") (pintype "output"))
      (node (ref "LED20") (pin "DI") (pinfunction "DI_DI") (pintype "input"))
    )
    (net (code "56") (name "Net-(LED20-PadDO)") (class "Default")
      (node (ref "LED20") (pin "DO") (pinfunction "DO_DO") (pintype "output"))
      (node (ref "LED21") (pin "DI") (pinfunction "DI_DI") (pintype "input"))
    )
    (net (code "57") (name "Net-(LED21-PadDO)") (class "Default")
      (node (ref "LED21") (pin "DO") (pinfunction "DO_DO") (pintype "output"))
      (node (ref "LED22") (pin "DI") (pinfunction "DI_DI") (pintype "input"))
    )
    (net (code "58") (name "Net-(LED22-PadDO)") (class "Default")
      (node (ref "LED22") (pin "DO") (pinfunction "DO_DO") (pintype "output"))
      (node (ref "LED23") (pin "DI") (pinfunction "DI_DI") (pintype "input"))
    )
    (net (code "59") (name "Net-(LED23-PadDO)") (class "Default")
      (node (ref "LED23") (pin "DO") (pinfunction "DO_DO") (pintype "output"))
      (node (ref "LED24") (pin "DI") (pinfunction "DI_DI") (pintype "input"))
    )
    (net (code "60") (name "Net-(LED24-PadDO)") (class "Default")
      (node (ref "LED24") (pin "DO") (pinfunction "DO_DO") (pintype "output"))
      (node (ref "LED25") (pin "DI") (pinfunction "DI_DI") (pintype "input"))
    )
    (net (code "61") (name "Net-(LED25-PadDO)") (class "Default")
      (node (ref "LED25") (pin "DO") (pinfunction "DO_DO") (pintype "output"))
      (node (ref "LED26") (pin "DI") (pinfunction "DI_DI") (pintype "input"))
    )
    (net (code "62") (name "Net-(LED26-PadDO)") (class "Default")
      (node (ref "LED26") (pin "DO") (pinfunction "DO_DO") (pintype "output"))
      (node (ref "LED27") (pin "DI") (pinfunction "DI_DI") (pintype "input"))
    )
    (net (code "63") (name "Net-(LED27-PadDO)") (class "Default")
      (node (ref "LED27") (pin "DO") (pinfunction "DO_DO") (pintype "output"))
      (node (ref "LED28") (pin "DI") (pinfunction "DI_DI") (pintype "input"))
    )
    (net (code "64") (name "Net-(LED28-PadDO)") (class "Default")
      (node (ref "LED28") (pin "DO") (pinfunction "DO_DO") (pintype "output"))
      (node (ref "LED29") (pin "DI") (pinfunction "DI_DI") (pintype "input"))
    )
    (net (code "65") (name "Net-(LED29-PadDO)") (class "Default")
      (node (ref "LED29") (pin "DO") (pinfunction "DO_DO") (pintype "output"))
      (node (ref "LED30") (pin "DI") (pinfunction "DI_DI") (pintype "input"))
    )
    (net (code "66") (name "Net-(LED30-PadDO)") (class "Default")
      (node (ref "LED30") (pin "DO") (pinfunction "DO_DO") (pintype "output"))
      (node (ref "LED31") (pin "DI") (pinfunction "DI_DI") (pintype "input"))
    )
    (net (code "67") (name "Net-(LED31-PadDO)") (class "Default")
      (node (ref "LED31") (pin "DO") (pinfunction "DO_DO") (pintype "output"))
      (node (ref "LED32") (pin "DI") (pinfunction "DI_DI") (pintype "input"))
    )
    (net (code "68") (name "Net-(LED32-PadDO)") (class "Default")
      (node (ref "LED32") (pin "DO") (pinfunction "DO_DO") (pintype "output"))
      (node (ref "LED33") (pin "DI") (pinfunction "DI_DI") (pintype "input"))
    )
    (net (code "69") (name "Net-(LED33-PadDO)") (class "Default")
      (node (ref "LED33") (pin "DO") (pinfunction "DO_DO") (pintype "output"))
      (node (ref "LED34") (pin "DI") (pinfunction "DI_DI") (pintype "input"))
    )
    (net (code "70") (name "Net-(LED34-PadDO)") (class "Default")
      (node (ref "LED34") (pin "DO") (pinfunction "DO_DO") (pintype "output"))
      (node (ref "LED35") (pin "DI") (pinfunction "DI_DI") (pintype "input"))
    )
    (net (code "71") (name "Net-(LED35-PadDO)") (class "Default")
      (node (ref "LED35") (pin "DO") (pinfunction "DO_DO") (pintype "output"))
      (node (ref "LED36") (pin "DI") (pinfunction "DI_DI") (pintype "input"))
    )
    (net (code "72") (name "Net-(LED36-PadDO)") (class "Default")
      (node (ref "LED36") (pin "DO") (pinfunction "DO_DO") (pintype "output"))
      (node (ref "LED37") (pin "DI") (pinfunction "DI_DI") (pintype "input"))
    )
    (net (code "73") (name "Net-(LED37-PadDO)") (class "Default")
      (node (ref "LED37") (pin "DO") (pinfunction "DO_DO") (pintype "output"))
      (node (ref "LED38") (pin "DI") (pinfunction "DI_DI") (pintype "input"))
    )
    (net (code "74") (name "Net-(LED38-PadDO)") (class "Default")
      (node (ref "LED38") (pin "DO") (pinfunction "DO_DO") (pintype "output"))
      (node (ref "LED39") (pin "DI") (pinfunction "DI_DI") (pintype "input"))
    )
    (net (code "75") (name "Net-(LED39-PadDO)") (class "Default")
      (node (ref "LED39") (pin "DO") (pinfunction "DO_DO") (pintype "output"))
      (node (ref "LED40") (pin "DI") (pinfunction "DI_DI") (pintype "input"))
    )
    (net (code "76") (name "Net-(LED40-PadDO)") (class "Default")
      (node (ref "LED40") (pin "DO") (pinfunction "DO_DO") (pintype "output"))
      (node (ref "LED41") (pin "DI") (pinfunction "DI_DI") (pintype "input"))
    )
    (net (code "77") (name "Net-(LED41-PadDO)") (class "Default")
      (node (ref "LED41") (pin "DO") (pinfunction "DO_DO") (pintype "output"))
      (node (ref "LED42") (pin "DI") (pinfunction "DI_DI") (pintype "input"))
    )
    (net (code "78") (name "Net-(LED42-PadDO)") (class "Default")
      (node (ref "LED42") (pin "DO") (pinfunction "DO_DO") (pintype "output"))
      (node (ref "LED43") (pin "DI") (pinfunction "DI_DI") (pintype "input"))
    )
    (net (code "79") (name "Net-(LED43-PadDO)") (class "Default")
      (node (ref "LED43") (pin "DO") (pinfunction "DO_DO") (pintype "output"))
      (node (ref "LED44") (pin "DI") (pinfunction "DI_DI") (pintype "input"))
    )
    (net (code "80") (name "Net-(LED44-PadDO)") (class "Default")
      (node (ref "LED44") (pin "DO") (pinfunction "DO_DO") (pintype "output"))
      (node (ref "LED45") (pin "DI") (pinfunction "DI_DI") (pintype "input"))
    )
    (net (code "81") (name "Net-(LED45-PadDO)") (class "Default")
      (node (ref "LED45") (pin "DO") (pinfunction "DO_DO") (pintype "output"))
      (node (ref "LED46") (pin "DI") (pinfunction "DI_DI") (pintype "input"))
    )
    (net (code "82") (name "Net-(LED46-PadDO)") (class "Default")
      (node (ref "LED46") (pin "DO") (pinfunction "DO_DO") (pintype "output"))
      (node (ref "LED47") (pin "DI") (pinfunction "DI_DI") (pintype "input"))
    )
    (net (code "83") (name "Net-(LED47-PadDO)") (class "Default")
      (node (ref "LED47") (pin "DO") (pinfunction "DO_DO") (pintype "output"))
      (node (ref "LED48") (pin "DI") (pinfunction "DI_DI") (pintype "input"))
    )
    (net (code "84") (name "Net-(LED48-PadDO)") (class "Default")
      (node (ref "LED48") (pin "DO") (pinfunction "DO_DO") (pintype "output"))
      (node (ref "LED49") (pin "DI") (pinfunction "DI_DI") (pintype "input"))
    )
    (net (code "85") (name "Net-(LED49-PadDO)") (class "Default")
      (node (ref "LED49") (pin "DO") (pinfunction "DO_DO") (pintype "output"))
      (node (ref "LED50") (pin "DI") (pinfunction "DI_DI") (pintype "input"))
    )
    (net (code "86") (name "Net-(LED50-PadDO)") (class "Default")
      (node (ref "LED50") (pin "DO") (pinfunction "DO_DO") (pintype "output"))
      (node (ref "LED51") (pin "DI") (pinfunction "DI_DI") (pintype "input"))
    )
    (net (code "87") (name "Net-(LED51-PadDO)") (class "Default")
      (node (ref "LED51") (pin "DO") (pinfunction "DO_DO") (pintype "output"))
      (node (ref "LED52") (pin "DI") (pinfunction "DI_DI") (pintype "input"))
    )
    (net (code "88") (name "Net-(LED52-PadDO)") (class "Default")
      (node (ref "LED52") (pin "DO") (pinfunction "DO_DO") (pintype "output"))
      (node (ref "LED53") (pin "DI") (pinfunction "DI_DI") (pintype "input"))
    )
    (net (code "89") (name "Net-(LED53-PadDO)") (class "Default")
      (node (ref "LED53") (pin "DO") (pinfunction "DO_DO") (pintype "output"))
      (node (ref "LED54") (pin "DI") (pinfunction "DI_DI") (pintype "input"))
    )
    (net (code "90") (name "Net-(LED54-PadDO)") (class "Default")
      (node (ref "LED54") (pin "DO") (pinfunction "DO_DO") (pintype "output"))
      (node (ref "LED55") (pin "DI") (pinfunction "DI_DI") (pintype "input"))
    )
    (net (code "91") (name "Net-(LED55-PadDO)") (class "Default")
      (node (ref "LED55") (pin "DO") (pinfunction "DO_DO") (pintype "output"))
      (node (ref "LED56") (pin "DI") (pinfunction "DI_DI") (pintype "input"))
    )
    (net (code "92") (name "Net-(LED56-PadDO)") (class "Default")
      (node (ref "LED56") (pin "DO") (pinfunction "DO_DO") (pintype "output"))
      (node (ref "LED57") (pin "DI") (pinfunction "DI_DI") (pintype "input"))
    )
    (net (code "93") (name "Net-(LED57-PadDO)") (class "Default")
      (node (ref "LED57") (pin "DO") (pinfunction "DO_DO") (pintype "output"))
      (node (ref "LED58") (pin "DI") (pinfunction "DI_DI") (pintype "input"))
    )
    (net (code "94") (name "Net-(LED58-PadDO)") (class "Default")
      (node (ref "LED58") (pin "DO") (pinfunction "DO_DO") (pintype "output"))
      (node (ref "LED59") (pin "DI") (pinfunction "DI_DI") (pintype "input"))
    )
    (net (code "95") (name "Net-(LED59-PadDO)") (class "Default")
      (node (ref "LED59") (pin "DO") (pinfunction "DO_DO") (pintype "output"))
      (node (ref "LED60") (pin "DI") (pinfunction "DI_DI") (pintype "input"))
    )
    (net (code "96") (name "Net-(LED61-PadDO)") (class "Default")
      (node (ref "LED61") (pin "DO") (pinfunction "DO_DO") (pintype "output"))
      (node (ref "LED62") (pin "DI") (pinfunction "DI_DI") (pintype "input"))
    )
    (net (code "97") (name "Net-(LED62-PadDO)") (class "Default")
      (node (ref "LED62") (pin "DO") (pinfunction "DO_DO") (pintype "output"))
      (node (ref "LED63") (pin "DI") (pinfunction "DI_DI") (pintype "input"))
    )
    (net (code "98") (name "Net-(LED63-PadDO)") (class "Default")
      (node (ref "LED63") (pin "DO") (pinfunction "DO_DO") (pintype "output"))
      (node (ref "LED64") (pin "DI") (pinfunction "DI_DI") (pintype "input"))
    )
    (net (code "99") (name "Net-(LED64-PadDO)") (class "Default")
      (node (ref "LED64") (pin "DO") (pinfunction "DO_DO") (pintype "output"))
      (node (ref "LED65") (pin "DI") (pinfunction "DI_DI") (pintype "input"))
    )
    (net (code "100") (name "Net-(LED65-PadDO)") (class "Default")
      (node (ref "LED65") (pin "DO") (pinfunction "DO_DO") (pintype "output"))
      (node (ref "LED66") (pin "DI") (pinfunction "DI_DI") (pintype "input"))
    )
    (net (code "101") (name "Net-(LED66-PadDO)") (class "Default")
      (node (ref "LED66") (pin "DO") (pinfunction "DO_DO") (pintype "output"))
      (node (ref "LED67") (pin "DI") (pinfunction "DI_DI") (pintype "input"))
    )
    (net (code "102") (name "Net-(LED67-PadDO)") (class "Default")
      (node (ref "LED67") (pin "DO") (pinfunction "DO_DO") (pintype "output"))
      (node (ref "LED68") (pin "DI") (pinfunction "DI_DI") (pintype "input"))
    )
    (net (code "103") (name "Net-(LED68-PadDO)") (class "Default")
      (node (ref "LED68") (pin "DO") (pinfunction "DO_DO") (pintype "output"))
      (node (ref "LED69") (pin "DI") (pinfunction "DI_DI") (pintype "input"))
    )
    (net (code "104") (name "Net-(LED69-PadDO)") (class "Default")
      (node (ref "LED69") (pin "DO") (pinfunction "DO_DO") (pintype "output"))
      (node (ref "LED70") (pin "DI") (pinfunction "DI_DI") (pintype "input"))
    )
    (net (code "105") (name "Net-(LED70-PadDO)") (class "Default")
      (node (ref "LED70") (pin "DO") (pinfunction "DO_DO") (pintype "output"))
      (node (ref "LED71") (pin "DI") (pinfunction "DI_DI") (pintype "input"))
    )
    (net (code "106") (name "Net-(LED71-PadDO)") (class "Default")
      (node (ref "LED71") (pin "DO") (pinfunction "DO_DO") (pintype "output"))
      (node (ref "LED72") (pin "DI") (pinfunction "DI_DI") (pintype "input"))
    )
    (net (code "107") (name "Net-(LED72-PadDO)") (class "Default")
      (node (ref "LED72") (pin "DO") (pinfunction "DO_DO") (pintype "output"))
      (node (ref "LED73") (pin "DI") (pinfunction "DI_DI") (pintype "input"))
    )
    (net (code "108") (name "Net-(LED73-PadDO)") (class "Default")
      (node (ref "LED73") (pin "DO") (pinfunction "DO_DO") (pintype "output"))
      (node (ref "LED74") (pin "DI") (pinfunction "DI_DI") (pintype "input"))
    )
    (net (code "109") (name "Net-(LED74-PadDO)") (class "Default")
      (node (ref "LED74") (pin "DO") (pinfunction "DO_DO") (pintype "output"))
      (node (ref "LED75") (pin "DI") (pinfunction "DI_DI") (pintype "input"))
    )
    (net (code "110") (name "Net-(LED75-PadDO)") (class "Default")
      (node (ref "LED75") (pin "DO") (pinfunction "DO_DO") (pintype "output"))
      (node (ref "LED76") (pin "DI") (pinfunction "DI_DI") (pintype "input"))
    )
    (net (code "111") (name "Net-(LED76-PadDO)") (class "Default")
      (node (ref "LED76") (pin "DO") (pinfunction "DO_DO") (pintype "output"))
      (node (ref "LED77") (pin "DI") (pinfunction "DI_DI") (pintype "input"))
    )
    (net (code "112") (name "Net-(LED77-PadDO)") (class "Default")
      (node (ref "LED77") (pin "DO") (pinfunction "DO_DO") (pintype "output"))
      (node (ref "LED78") (pin "DI") (pinfunction "DI_DI") (pintype "input"))
    )
    (net (code "113") (name "Net-(LED78-PadDO)") (class "Default")
      (node (ref "LED78") (pin "DO") (pinfunction "DO_DO") (pintype "output"))
      (node (ref "LED79") (pin "DI") (pinfunction "DI_DI") (pintype "input"))
    )
    (net (code "114") (name "Net-(LED79-PadDO)") (class "Default")
      (node (ref "LED79") (pin "DO") (pinfunction "DO_DO") (pintype "output"))
      (node (ref "LED80") (pin "DI") (pinfunction "DI_DI") (pintype "input"))
    )
    (net (code "115") (name "Net-(LED80-PadDO)") (class "Default")
      (node (ref "LED80") (pin "DO") (pinfunction "DO_DO") (pintype "output"))
      (node (ref "LED81") (pin "DI") (pinfunction "DI_DI") (pintype "input"))
    )
    (net (code "116") (name "Net-(LED81-PadDO)") (class "Default")
      (node (ref "LED81") (pin "DO") (pinfunction "DO_DO") (pintype "output"))
      (node (ref "LED82") (pin "DI") (pinfunction "DI_DI") (pintype "input"))
    )
    (net (code "117") (name "Net-(LED82-PadDO)") (class "Default")
      (node (ref "LED82") (pin "DO") (pinfunction "DO_DO") (pintype "output"))
      (node (ref "LED83") (pin "DI") (pinfunction "DI_DI") (pintype "input"))
    )
    (net (code "118") (name "Net-(LED83-PadDO)") (class "Default")
      (node (ref "LED83") (pin "DO") (pinfunction "DO_DO") (pintype "output"))
      (node (ref "LED84") (pin "DI") (pinfunction "DI_DI") (pintype "input"))
    )
    (net (code "119") (name "Net-(LED84-PadDO)") (class "Default")
      (node (ref "LED84") (pin "DO") (pinfunction "DO_DO") (pintype "output"))
      (node (ref "LED85") (pin "DI") (pinfunction "DI_DI") (pintype "input"))
    )
    (net (code "120") (name "Net-(LED85-PadDO)") (class "Default")
      (node (ref "LED85") (pin "DO") (pinfunction "DO_DO") (pintype "output"))
      (node (ref "LED86") (pin "DI") (pinfunction "DI_DI") (pintype "input"))
    )
    (net (code "121") (name "Net-(LED86-PadDO)") (class "Default")
      (node (ref "LED86") (pin "DO") (pinfunction "DO_DO") (pintype "output"))
      (node (ref "LED87") (pin "DI") (pinfunction "DI_DI") (pintype "input"))
    )
    (net (code "122") (name "Net-(LED87-PadDO)") (class "Default")
      (node (ref "LED87") (pin "DO") (pinfunction "DO_DO") (pintype "output"))
      (node (ref "LED88") (pin "DI") (pinfunction "DI_DI") (pintype "input"))
    )
    (net (code "123") (name "Net-(LED88-PadDO)") (class "Default")
      (node (ref "LED88") (pin "DO") (pinfunction "DO_DO") (pintype "output"))
      (node (ref "LED89") (pin "DI") (pinfunction "DI_DI") (pintype "input"))
    )
    (net (code "124") (name "Net-(LED89-PadDO)") (class "Default")
      (node (ref "LED89") (pin "DO") (pinfunction "DO_DO") (pintype "output"))
      (node (ref "LED90") (pin "DI") (pinfunction "DI_DI") (pintype "input"))
    )
    (net (code "125") (name "Net-(LED90-PadDO)") (class "Default")
      (node (ref "LED90") (pin "DO") (pinfunction "DO_DO") (pintype "output"))
      (node (ref "LED91") (pin "DI") (pinfunction "DI_DI") (pintype "input"))
    )
    (net (code "126") (name "Net-(LED91-PadDO)") (class "Default")
      (node (ref "LED91") (pin "DO") (pinfunction "DO_DO") (pintype "output"))
      (node (ref "LED92") (pin "DI") (pinfunction "DI_DI") (pintype "input"))
    )
    (net (code "127") (name "Net-(LED92-PadDO)") (class "Default")
      (node (ref "LED92") (pin "DO") (pinfunction "DO_DO") (pintype "output"))
      (node (ref "LED93") (pin "DI") (pinfunction "DI_DI") (pintype "input"))
    )
    (net (code "128") (name "Net-(LED93-PadDO)") (class "Default")
      (node (ref "LED93") (pin "DO") (pinfunction "DO_DO") (pintype "output"))
      (node (ref "LED94") (pin "DI") (pinfunction "DI_DI") (pintype "input"))
    )
    (net (code "129") (name "Net-(LED94-PadDO)") (class "Default")
      (node (ref "LED94") (pin "DO") (pinfunction "DO_DO") (pintype "output"))
      (node (ref "LED95") (pin "DI") (pinfunction "DI_DI") (pintype "input"))
    )
    (net (code "130") (name "Net-(LED95-PadDO)") (class "Default")
      (node (ref "LED95") (pin "DO") (pinfunction "DO_DO") (pintype "output"))
      (node (ref "LED96") (pin "DI") (pinfunction "DI_DI") (pintype "input"))
    )
    (net (code "131") (name "Net-(LED96-PadDO)") (class "Default")
      (node (ref "LED96") (pin "DO") (pinfunction "DO_DO") (pintype "output"))
      (node (ref "LED97") (pin "DI") (pinfunction "DI_DI") (pintype "input"))
    )
    (net (code "132") (name "Net-(LED97-PadDO)") (class "Default")
      (node (ref "LED97") (pin "DO") (pinfunction "DO_DO") (pintype "output"))
      (node (ref "LED98") (pin "DI") (pinfunction "DI_DI") (pintype "input"))
    )
    (net (code "133") (name "Net-(LED98-PadDO)") (class "Default")
      (node (ref "LED98") (pin "DO") (pinfunction "DO_DO") (pintype "output"))
      (node (ref "LED99") (pin "DI") (pinfunction "DI_DI") (pintype "input"))
    )
    (net (code "134") (name "Net-(LED100-PadDI)") (class "Default")
      (node (ref "LED100") (pin "DI") (pinfunction "DI_DI") (pintype "input"))
      (node (ref "LED99") (pin "DO") (pinfunction "DO_DO") (pintype "output"))
    )
    (net (code "135") (name "Net-(LED100-PadDO)") (class "Default")
      (node (ref "LED100") (pin "DO") (pinfunction "DO_DO") (pintype "output"))
      (node (ref "LED101") (pin "DI") (pinfunction "DI_DI") (pintype "input"))
    )
    (net (code "136") (name "Net-(LED101-PadDO)") (class "Default")
      (node (ref "LED101") (pin "DO") (pinfunction "DO_DO") (pintype "output"))
      (node (ref "LED102") (pin "DI") (pinfunction "DI_DI") (pintype "input"))
    )
    (net (code "137") (name "Net-(LED102-PadDO)") (class "Default")
      (node (ref "LED102") (pin "DO") (pinfunction "DO_DO") (pintype "output"))
      (node (ref "LED103") (pin "DI") (pinfunction "DI_DI") (pintype "input"))
    )
    (net (code "138") (name "Net-(LED103-PadDO)") (class "Default")
      (node (ref "LED103") (pin "DO") (pinfunction "DO_DO") (pintype "output"))
      (node (ref "LED104") (pin "DI") (pinfunction "DI_DI") (pintype "input"))
    )
    (net (code "139") (name "Net-(LED104-PadDO)") (class "Default")
      (node (ref "LED104") (pin "DO") (pinfunction "DO_DO") (pintype "output"))
      (node (ref "LED105") (pin "DI") (pinfunction "DI_DI") (pintype "input"))
    )
    (net (code "140") (name "Net-(LED105-PadDO)") (class "Default")
      (node (ref "LED105") (pin "DO") (pinfunction "DO_DO") (pintype "output"))
      (node (ref "LED106") (pin "DI") (pinfunction "DI_DI") (pintype "input"))
    )
    (net (code "141") (name "Net-(LED106-PadDO)") (class "Default")
      (node (ref "LED106") (pin "DO") (pinfunction "DO_DO") (pintype "output"))
      (node (ref "LED107") (pin "DI") (pinfunction "DI_DI") (pintype "input"))
    )
    (net (code "142") (name "Net-(LED107-PadDO)") (class "Default")
      (node (ref "LED107") (pin "DO") (pinfunction "DO_DO") (pintype "output"))
      (node (ref "LED108") (pin "DI") (pinfunction "DI_DI") (pintype "input"))
    )
    (net (code "143") (name "Net-(LED108-PadDO)") (class "Default")
      (node (ref "LED108") (pin "DO") (pinfunction "DO_DO") (pintype "output"))
      (node (ref "LED109") (pin "DI") (pinfunction "DI_DI") (pintype "input"))
    )
    (net (code "144") (name "Net-(LED109-PadDO)") (class "Default")
      (node (ref "LED109") (pin "DO") (pinfunction "DO_DO") (pintype "output"))
      (node (ref "LED110") (pin "DI") (pinfunction "DI_DI") (pintype "input"))
    )
    (net (code "145") (name "Net-(LED110-PadDO)") (class "Default")
      (node (ref "LED110") (pin "DO") (pinfunction "DO_DO") (pintype "output"))
      (node (ref "LED111") (pin "DI") (pinfunction "DI_DI") (pintype "input"))
    )
    (net (code "146") (name "Net-(LED111-PadDO)") (class "Default")
      (node (ref "LED111") (pin "DO") (pinfunction "DO_DO") (pintype "output"))
      (node (ref "LED112") (pin "DI") (pinfunction "DI_DI") (pintype "input"))
    )
    (net (code "147") (name "Net-(LED112-PadDO)") (class "Default")
      (node (ref "LED112") (pin "DO") (pinfunction "DO_DO") (pintype "output"))
      (node (ref "LED113") (pin "DI") (pinfunction "DI_DI") (pintype "input"))
    )
    (net (code "148") (name "Net-(LED113-PadDO)") (class "Default")
      (node (ref "LED113") (pin "DO") (pinfunction "DO_DO") (pintype "output"))
      (node (ref "LED114") (pin "DI") (pinfunction "DI_DI") (pintype "input"))
    )
    (net (code "149") (name "Net-(LED114-PadDO)") (class "Default")
      (node (ref "LED114") (pin "DO") (pinfunction "DO_DO") (pintype "output"))
      (node (ref "LED115") (pin "DI") (pinfunction "DI_DI") (pintype "input"))
    )
    (net (code "150") (name "Net-(LED115-PadDO)") (class "Default")
      (node (ref "LED115") (pin "DO") (pinfunction "DO_DO") (pintype "output"))
      (node (ref "LED116") (pin "DI") (pinfunction "DI_DI") (pintype "input"))
    )
    (net (code "151") (name "Net-(LED116-PadDO)") (class "Default")
      (node (ref "LED116") (pin "DO") (pinfunction "DO_DO") (pintype "output"))
      (node (ref "LED117") (pin "DI") (pinfunction "DI_DI") (pintype "input"))
    )
    (net (code "152") (name "Net-(LED117-PadDO)") (class "Default")
      (node (ref "LED117") (pin "DO") (pinfunction "DO_DO") (pintype "output"))
      (node (ref "LED118") (pin "DI") (pinfunction "DI_DI") (pintype "input"))
    )
    (net (code "153") (name "Net-(LED118-PadDO)") (class "Default")
      (node (ref "LED118") (pin "DO") (pinfunction "DO_DO") (pintype "output"))
      (node (ref "LED119") (pin "DI") (pinfunction "DI_DI") (pintype "input"))
    )
    (net (code "154") (name "Net-(LED119-PadDO)") (class "Default")
      (node (ref "LED119") (pin "DO") (pinfunction "DO_DO") (pintype "output"))
      (node (ref "LED120") (pin "DI") (pinfunction "DI_DI") (pintype "input"))
    )
  )
)
